# OpenROV_Controller_2_7.net
KiCad netlist of a schematic drawn in EAGLE
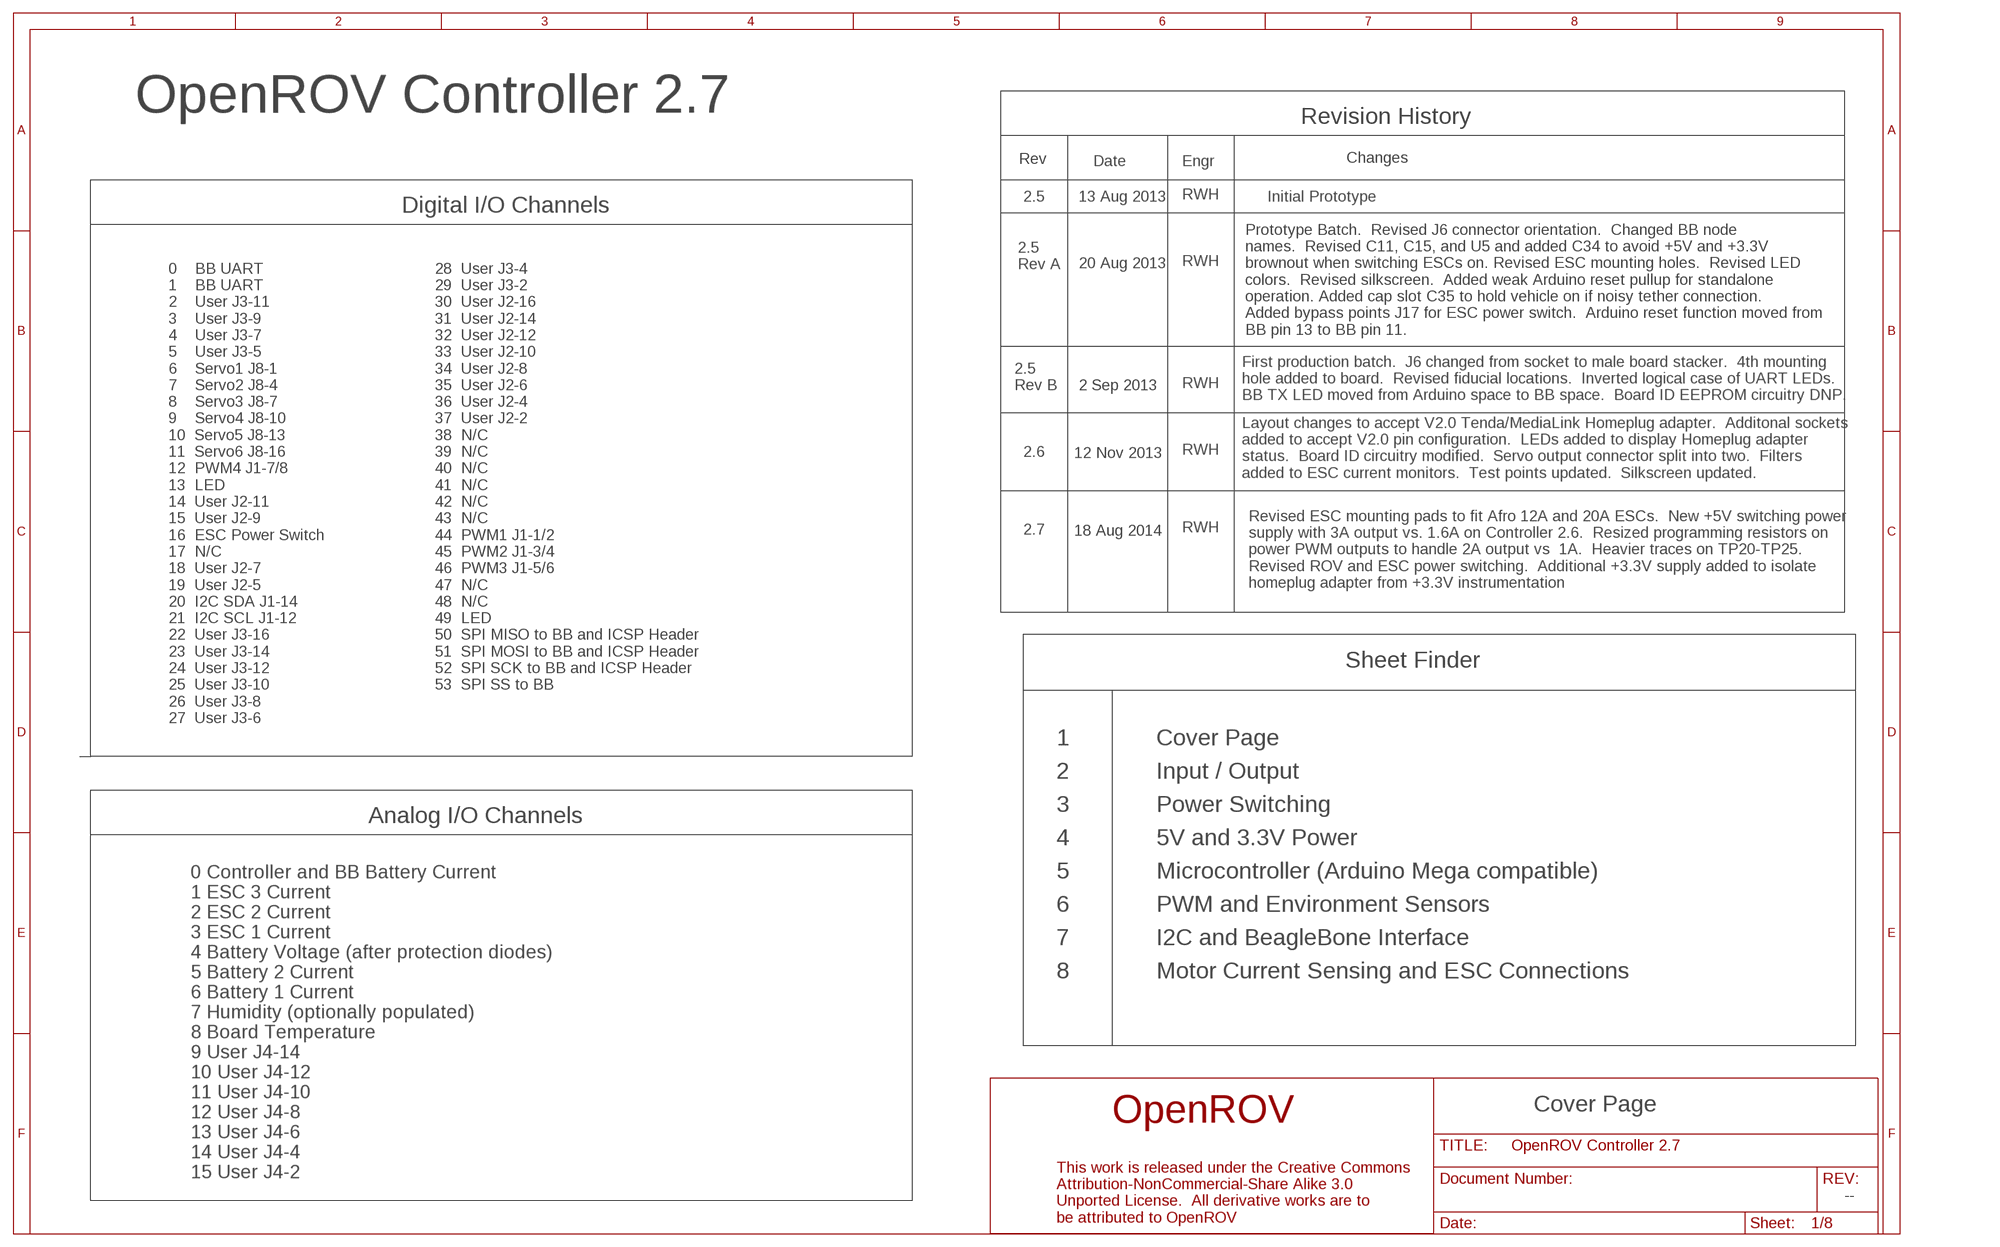
[diagram p0: schematic, sheet 1]
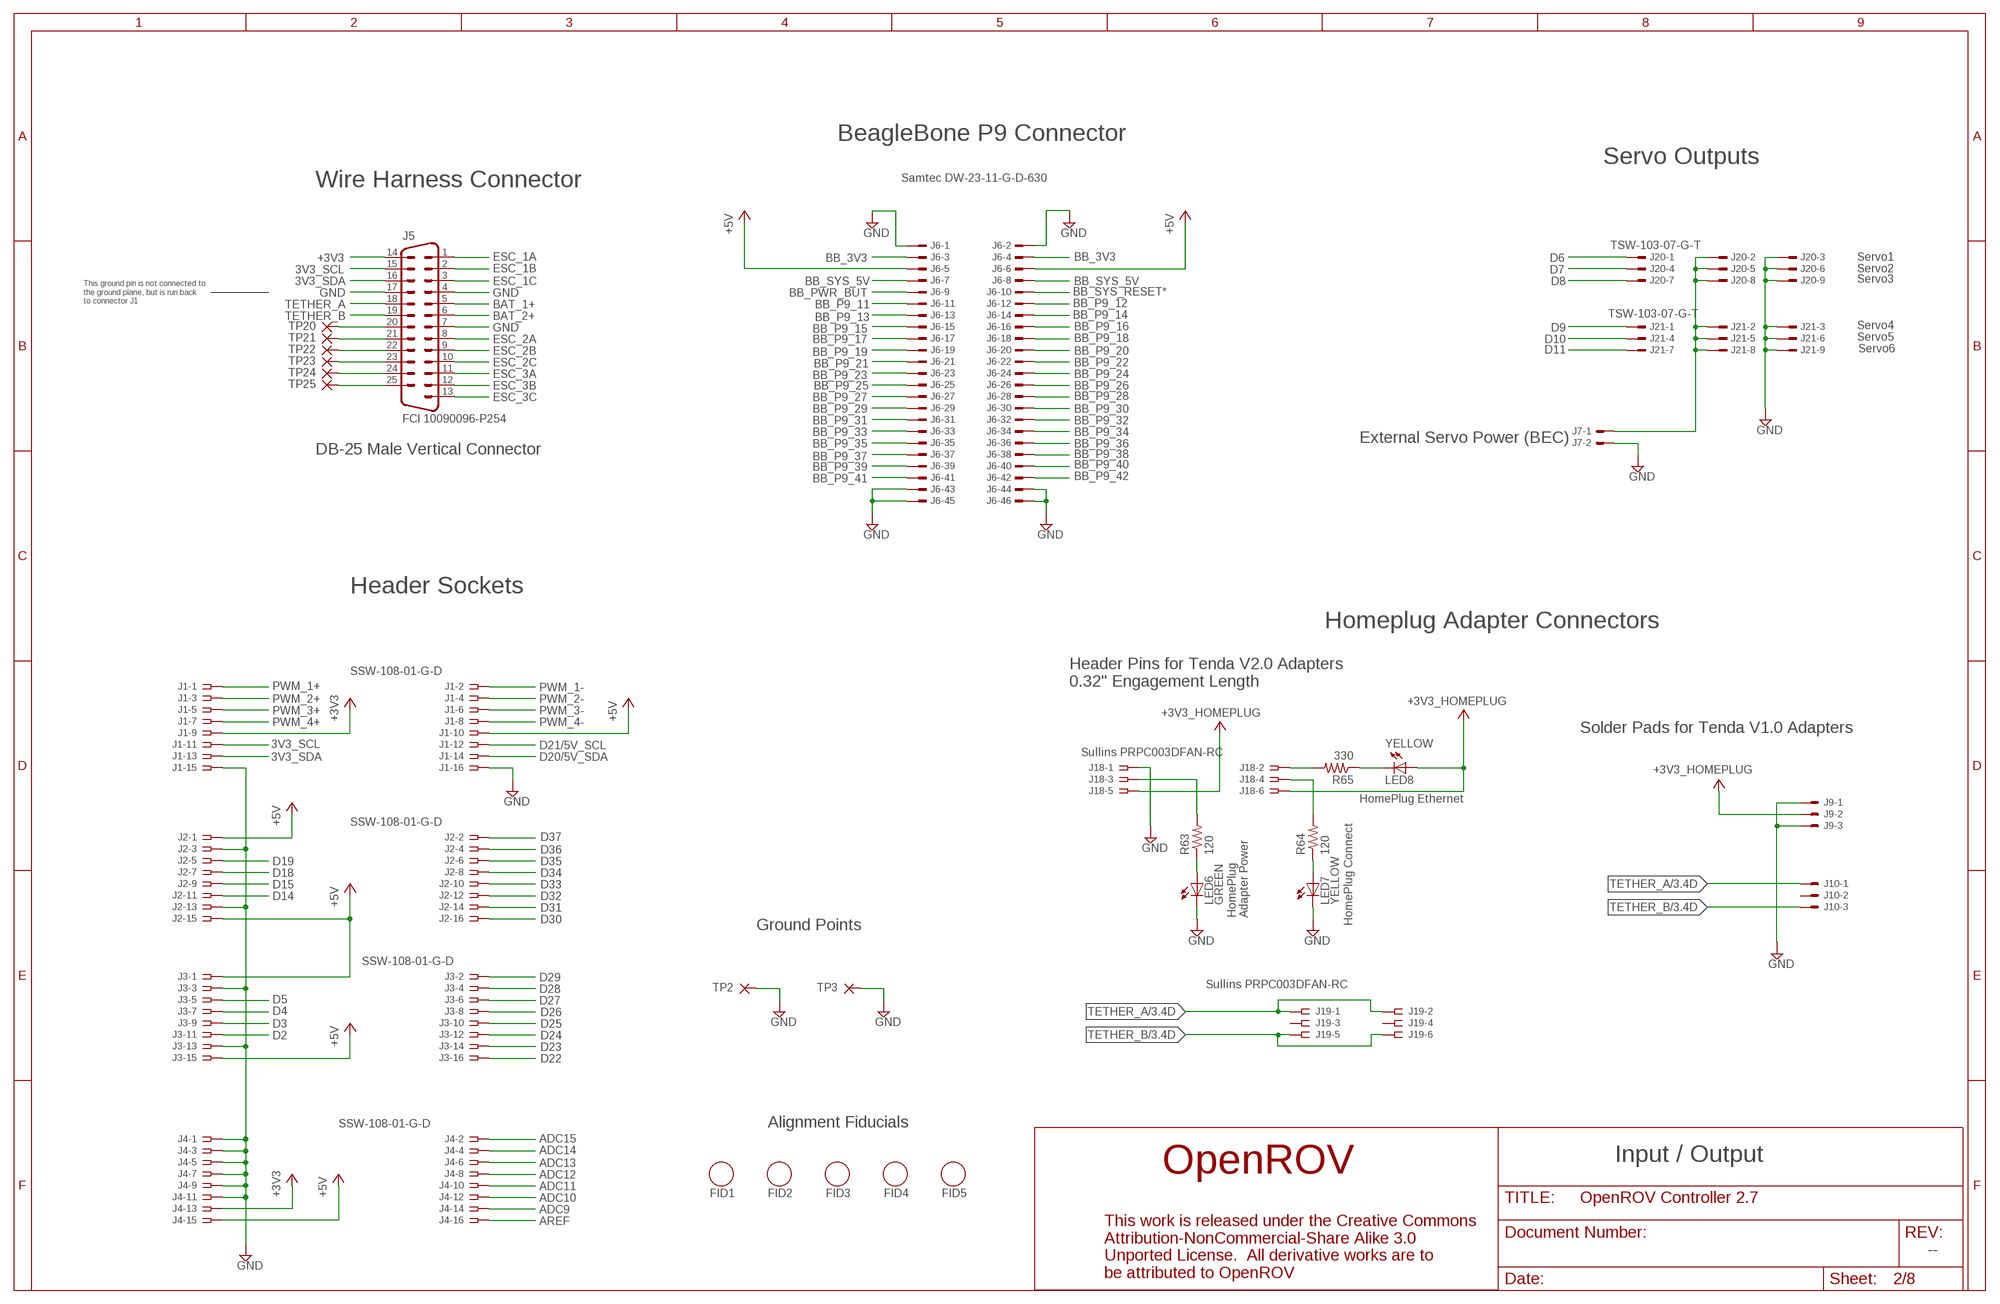
[diagram p1: schematic, sheet 2]
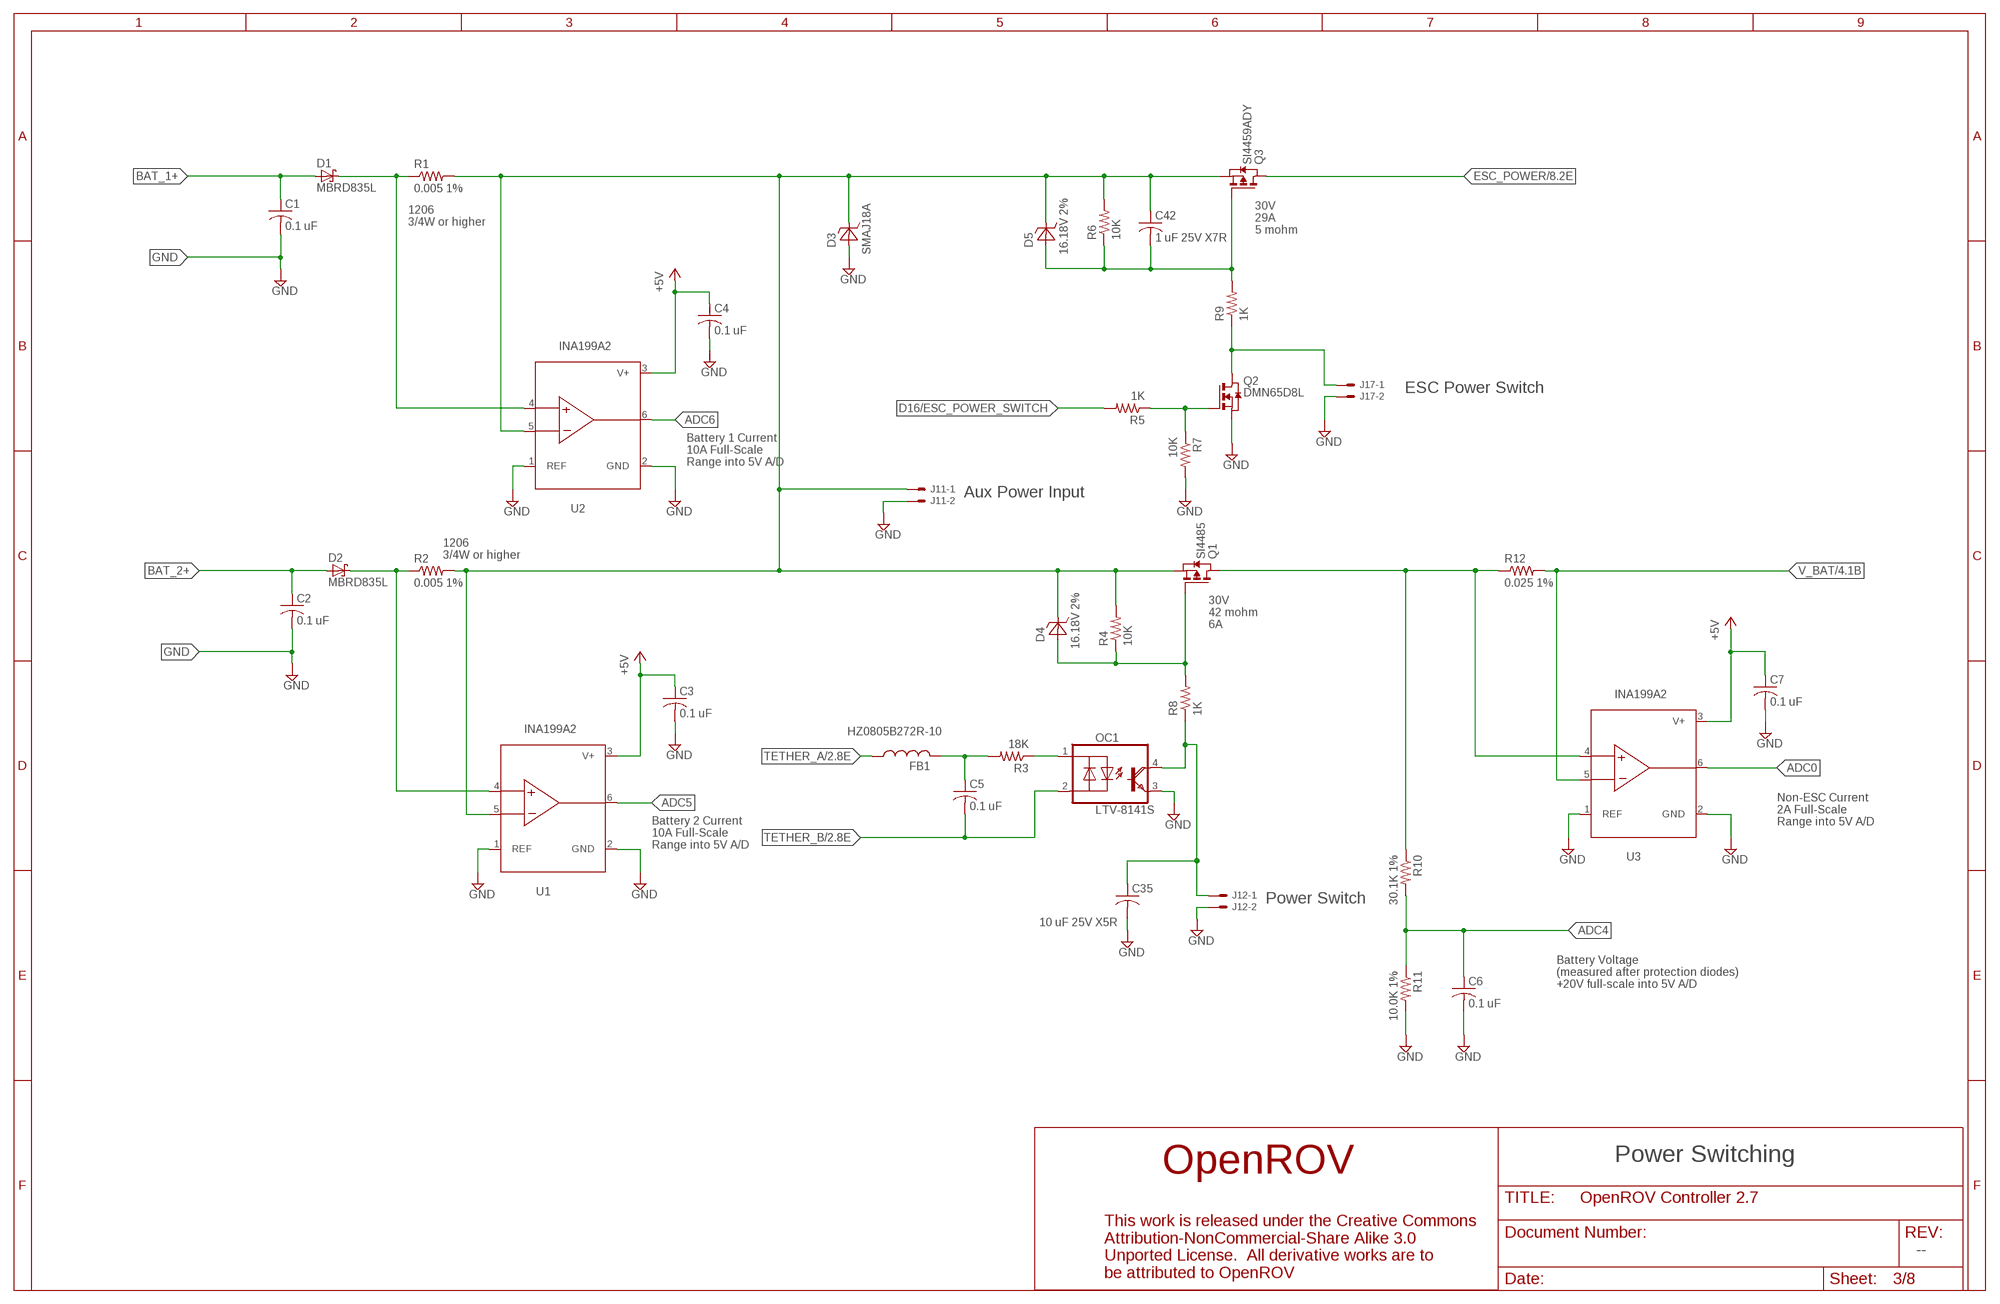
[diagram p2: schematic, sheet 3]
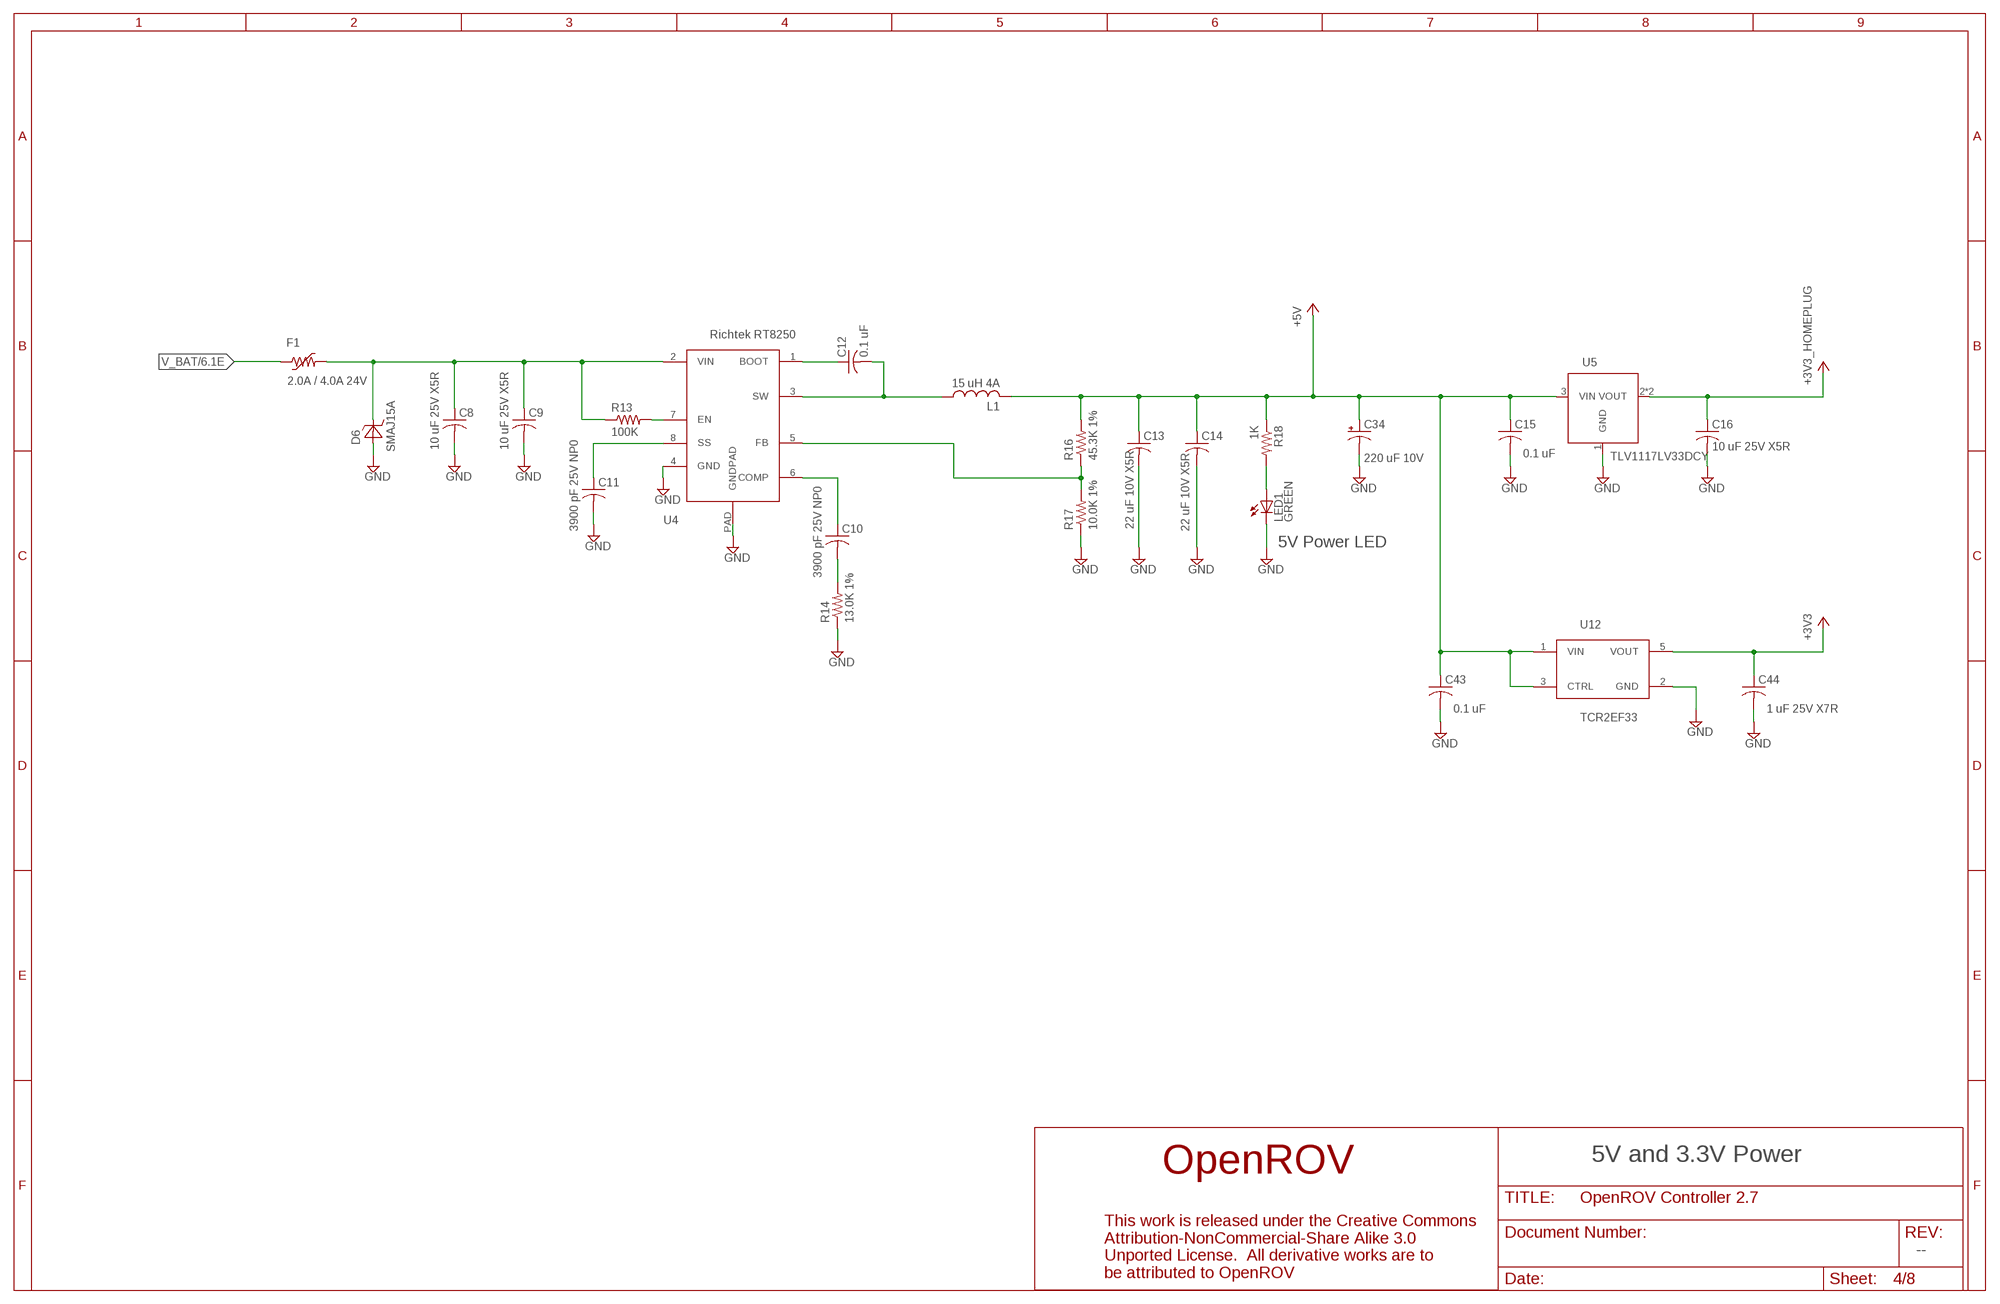
[diagram p3: schematic, sheet 4]
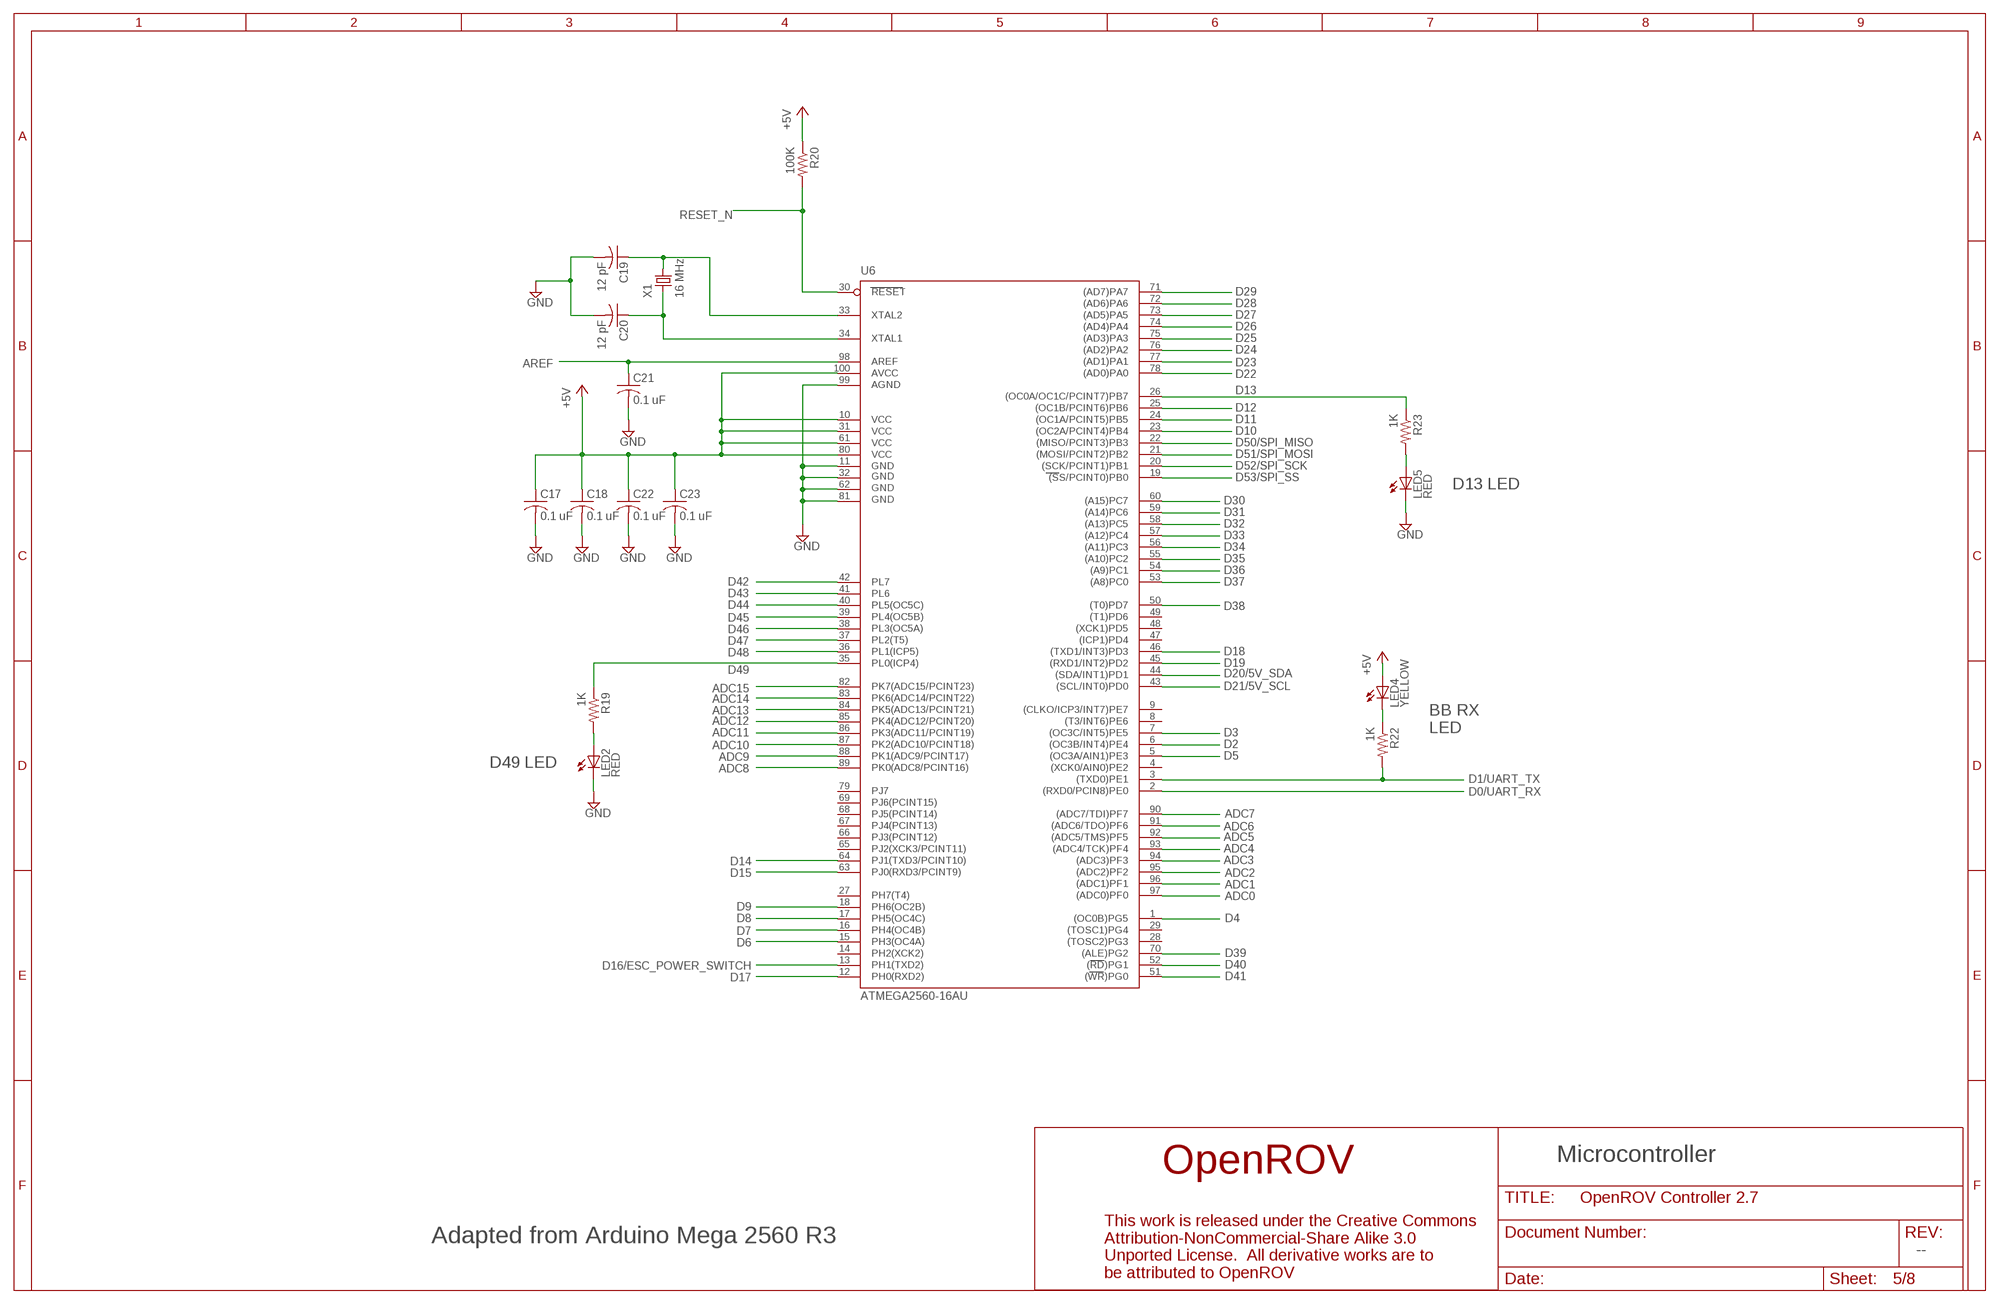
[diagram p4: schematic, sheet 5]
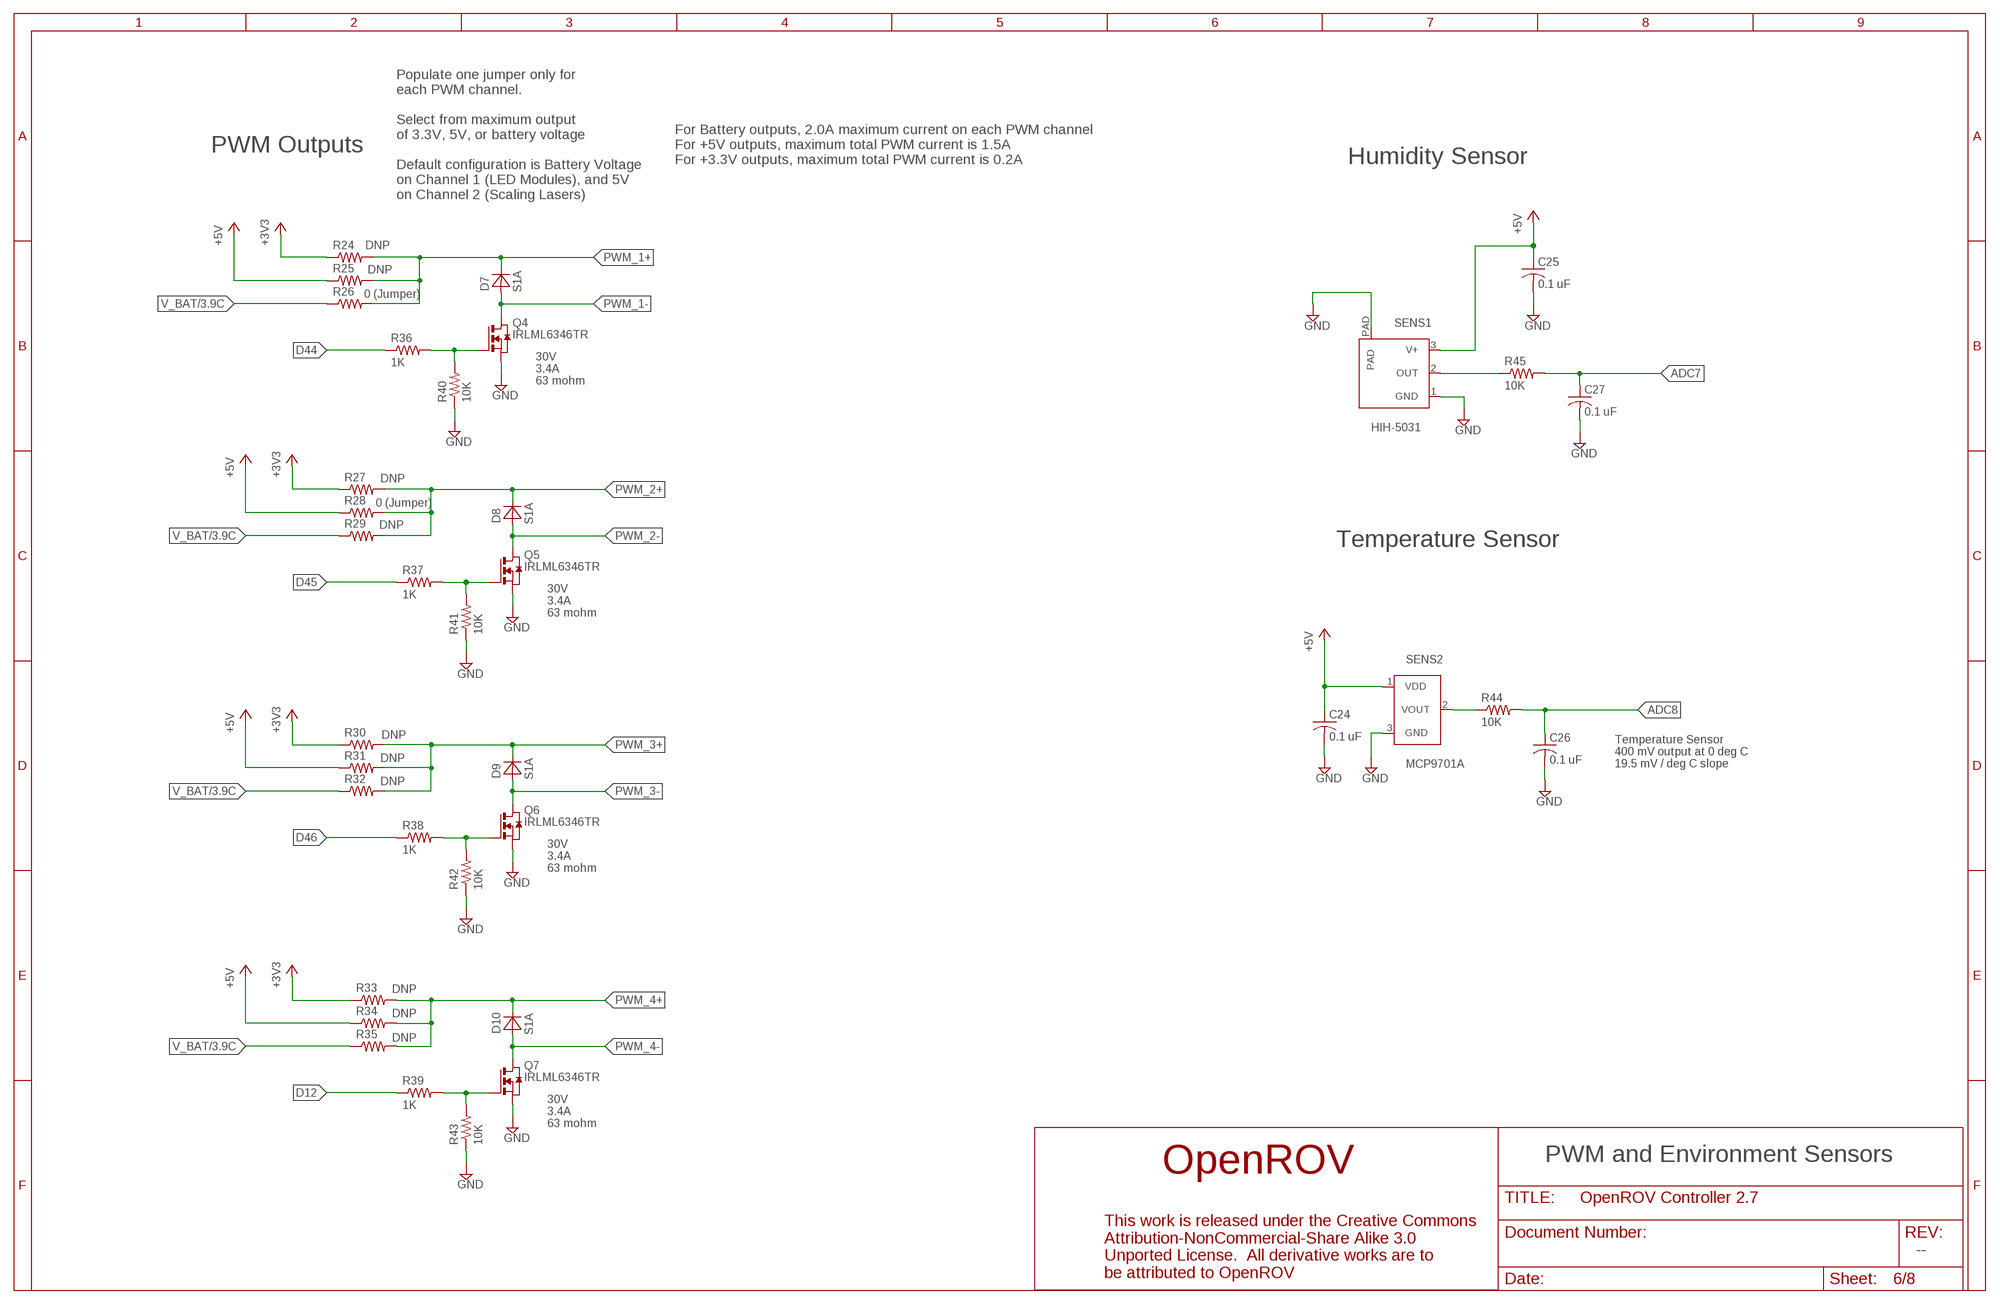
[diagram p5: schematic, sheet 6]
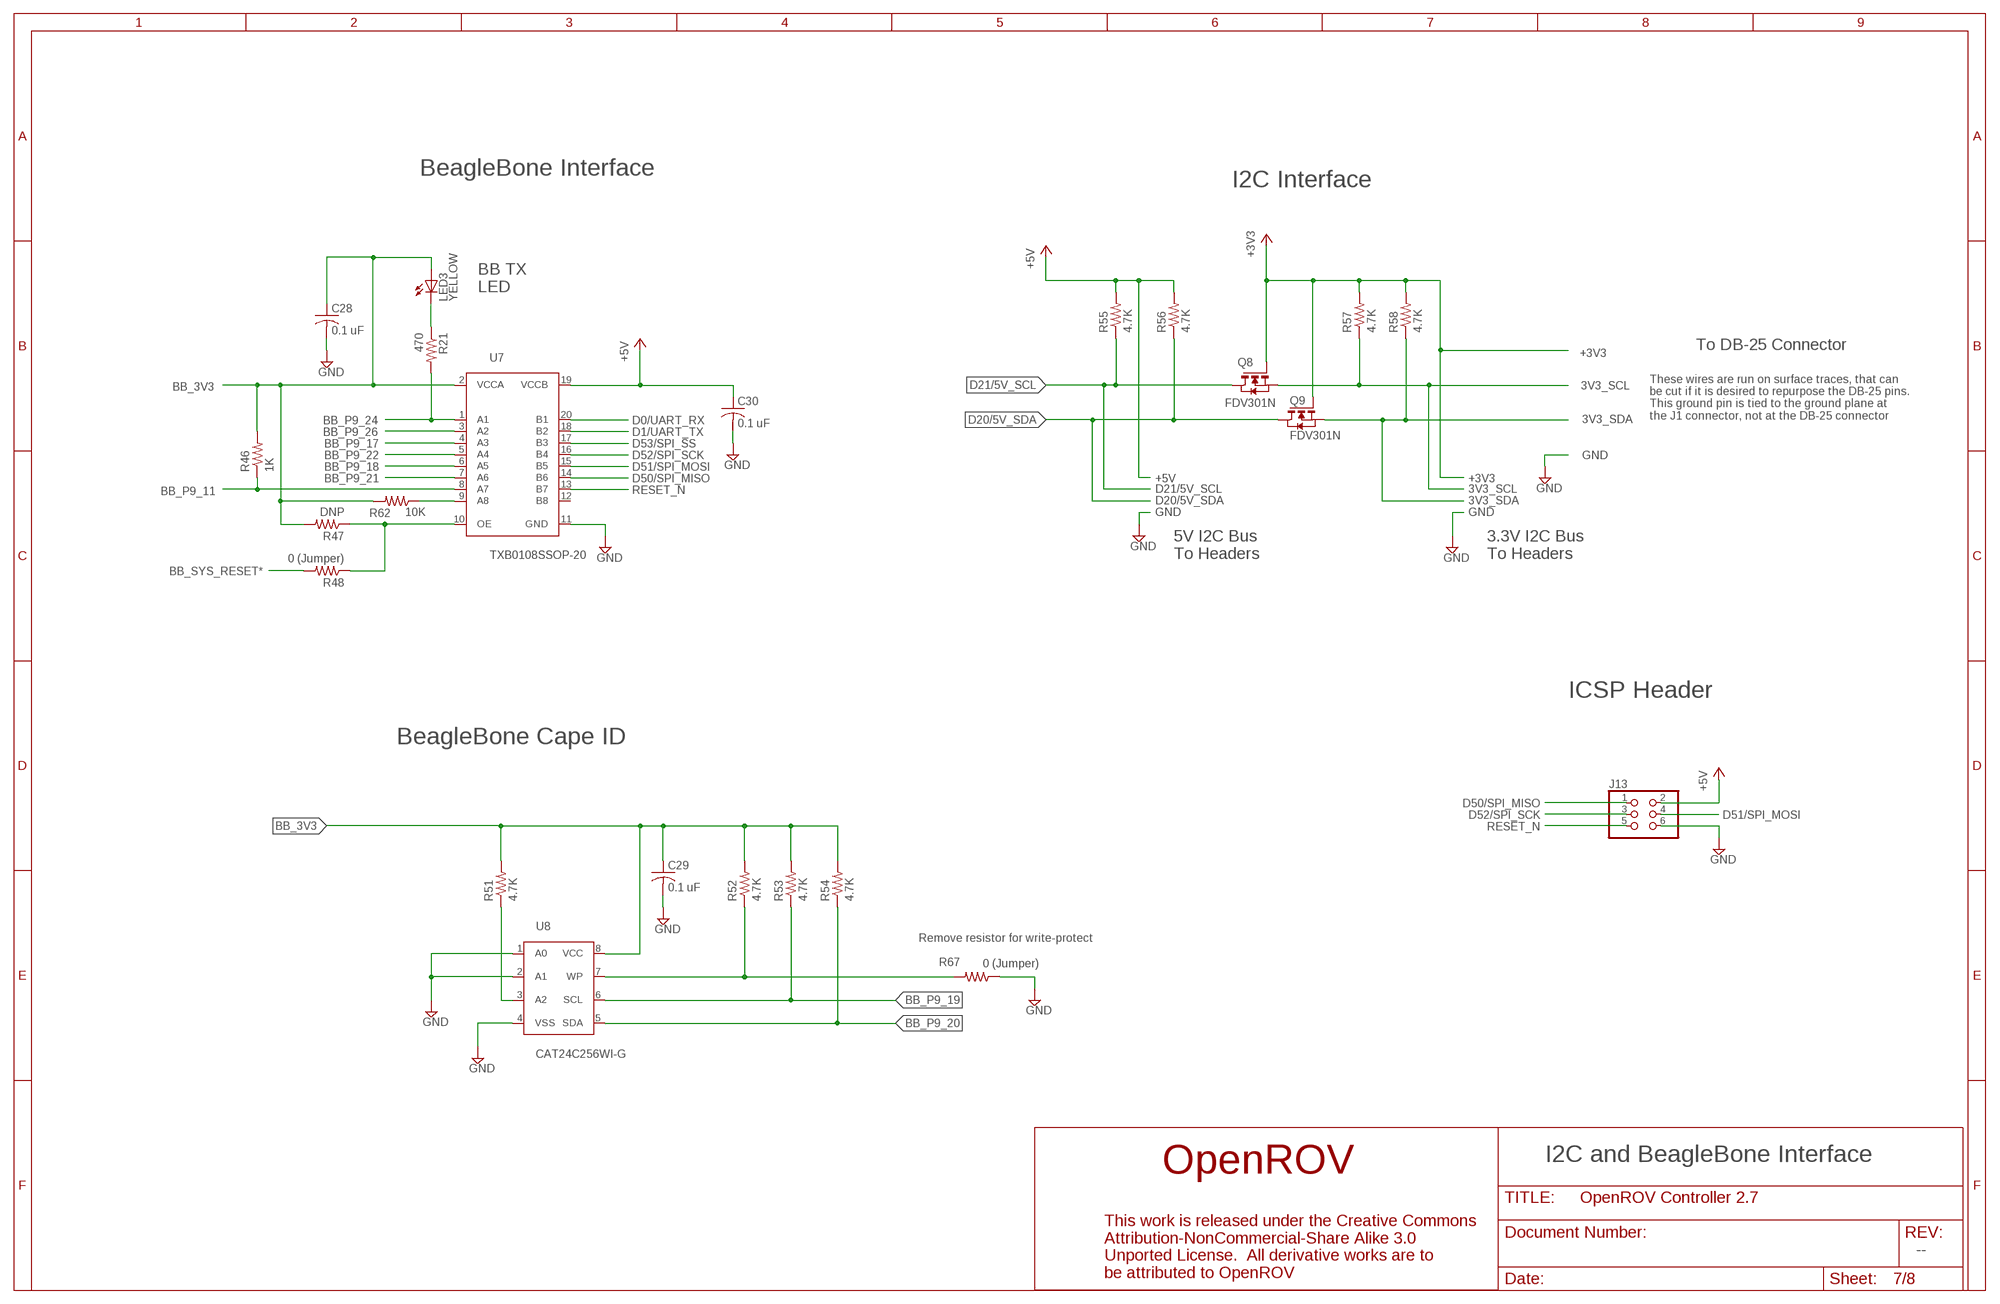
[diagram p6: schematic, sheet 7]
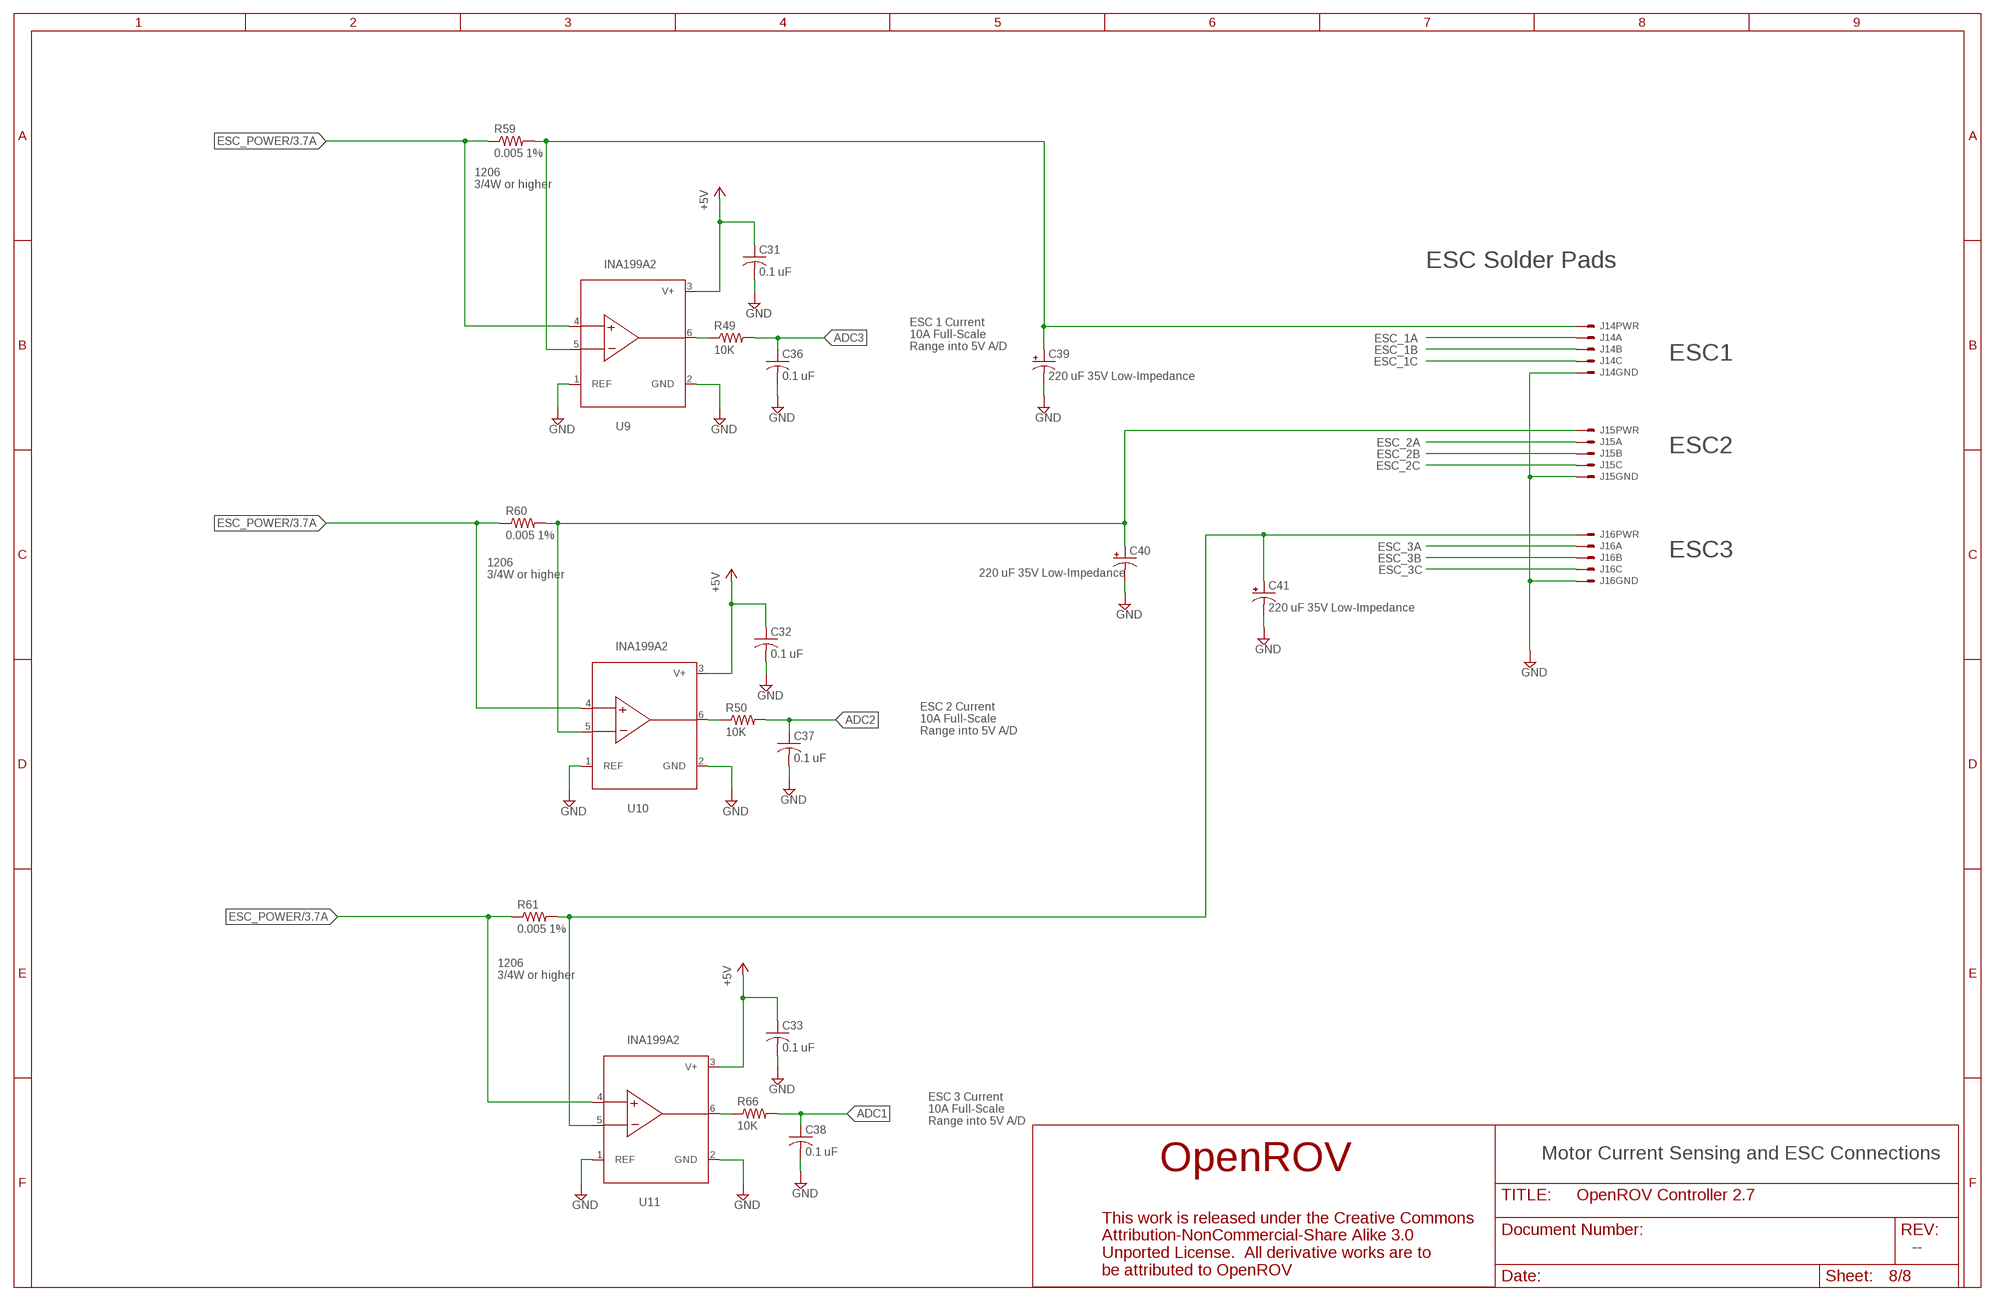
[diagram p7: schematic, sheet 8]

(export (version "E")
  (design (tool "Eeschema 10.0.6"))
  (components
    (comp (ref "FID1")
      (value "FIDUCIAL_1")
      (footprint "eagle-import:FIDUCIAL_1")
      (libsource (lib "eagle-import") (part "FIDUCIAL_1"))
    )
    (comp (ref "FID2")
      (value "FIDUCIAL_1")
      (footprint "eagle-import:FIDUCIAL_1")
      (libsource (lib "eagle-import") (part "FIDUCIAL_1"))
    )
    (comp (ref "FID3")
      (value "FIDUCIAL_1")
      (footprint "eagle-import:FIDUCIAL_1")
      (libsource (lib "eagle-import") (part "FIDUCIAL_1"))
    )
    (comp (ref "FID4")
      (value "FIDUCIAL_1")
      (footprint "eagle-import:FIDUCIAL_1")
      (libsource (lib "eagle-import") (part "FIDUCIAL_1"))
    )
    (comp (ref "FID5")
      (value "FIDUCIAL_1")
      (footprint "eagle-import:FIDUCIAL_1")
      (libsource (lib "eagle-import") (part "FIDUCIAL_1"))
    )
    (comp (ref "J1")
      (value "SSW-108-01-G-D")
      (footprint "eagle-import:SSW-108-02-S-D")
      (fields (field (name "MPN") "SSW-108-02-S-D"))
      (libsource (lib "eagle-import") (part "HDR_SOCKET_2X8"))
    )
    (comp (ref "J2")
      (value "SSW-108-01-G-D")
      (footprint "eagle-import:SSW-108-02-S-D")
      (fields (field (name "MPN") "SSW-108-02-S-D"))
      (libsource (lib "eagle-import") (part "HDR_SOCKET_2X8"))
    )
    (comp (ref "J3")
      (value "SSW-108-01-G-D")
      (footprint "eagle-import:SSW-108-02-S-D")
      (fields (field (name "MPN") "SSW-108-02-S-D"))
      (libsource (lib "eagle-import") (part "HDR_SOCKET_2X8"))
    )
    (comp (ref "J4")
      (value "SSW-108-01-G-D")
      (footprint "eagle-import:SSW-108-02-S-D")
      (fields (field (name "MPN") "SSW-108-02-S-D"))
      (libsource (lib "eagle-import") (part "HDR_SOCKET_2X8"))
    )
    (comp (ref "J5")
      (value "FCI 10090096-P254")
      (footprint "eagle-import:M25VP")
      (libsource (lib "eagle-import") (part "M25VP"))
    )
    (comp (ref "J6")
      (value "Samtec DW-23-11-G-D-630")
      (footprint "eagle-import:TSW-123-02-S-D")
      (libsource (lib "eagle-import") (part "BEAGLEBONE_PIN_HEADER"))
    )
    (comp (ref "J7")
      (value "HDR_1X2X0.100-ALT_SILK")
      (footprint "eagle-import:22-23-2021_ALT_SILK")
      (libsource (lib "eagle-import") (part "HDR_1X2X0.100-ALT_SILK"))
    )
    (comp (ref "J9")
      (value "HDR_1X3X0.100-ALT_SILK")
      (footprint "eagle-import:22-23-2031_ALT_SILK")
      (libsource (lib "eagle-import") (part "HDR_1X3X0.100-ALT_SILK"))
    )
    (comp (ref "J10")
      (value "HDR_1X3X0.100-ALT_SILK")
      (footprint "eagle-import:22-23-2031_ALT_SILK")
      (libsource (lib "eagle-import") (part "HDR_1X3X0.100-ALT_SILK"))
    )
    (comp (ref "J18")
      (value "Sullins PRPC003DFAN-RC")
      (footprint "eagle-import:SSW-103-02-S-D")
      (fields (field (name "MPN") "SSW-103-02-S-D"))
      (libsource (lib "eagle-import") (part "HDR_SOCKET_2X3"))
    )
    (comp (ref "J19")
      (value "Sullins PRPC003DFAN-RC")
      (footprint "eagle-import:SSW-103-02-S-D")
      (fields (field (name "MPN") "SSW-103-02-S-D"))
      (libsource (lib "eagle-import") (part "HDR_SOCKET_2X3"))
    )
    (comp (ref "J20")
      (value "TSW-103-07-G-T")
      (footprint "eagle-import:HDR_PINS_3X3")
      (libsource (lib "eagle-import") (part "HDR_PINS_3X3{dblquote}"))
    )
    (comp (ref "J21")
      (value "TSW-103-07-G-T")
      (footprint "eagle-import:HDR_PINS_3X3")
      (libsource (lib "eagle-import") (part "HDR_PINS_3X3{dblquote}"))
    )
    (comp (ref "LED6")
      (value "GREEN")
      (footprint "eagle-import:LED_CHIPLED_0603")
      (libsource (lib "eagle-import") (part "LED-0603"))
    )
    (comp (ref "LED7")
      (value "YELLOW")
      (footprint "eagle-import:LED_CHIPLED_0603")
      (libsource (lib "eagle-import") (part "LED-0603"))
    )
    (comp (ref "LED8")
      (value "YELLOW")
      (footprint "eagle-import:LED_CHIPLED_0603")
      (libsource (lib "eagle-import") (part "LED-0603"))
    )
    (comp (ref "R63")
      (value "120")
      (footprint "eagle-import:R0603")
      (libsource (lib "eagle-import") (part "RESISTOR-0603"))
    )
    (comp (ref "R64")
      (value "120")
      (footprint "eagle-import:R0603")
      (libsource (lib "eagle-import") (part "RESISTOR-0603"))
    )
    (comp (ref "R65")
      (value "330")
      (footprint "eagle-import:R0603")
      (libsource (lib "eagle-import") (part "RESISTOR-0603"))
    )
    (comp (ref "TP2")
      (value "TEST_PAD-1.0")
      (footprint "eagle-import:2.0_1.0")
      (libsource (lib "eagle-import") (part "TEST_PAD-1.0"))
    )
    (comp (ref "TP3")
      (value "TEST_PAD-1.0")
      (footprint "eagle-import:2.0_1.0")
      (libsource (lib "eagle-import") (part "TEST_PAD-1.0"))
    )
    (comp (ref "TP20")
      (value "TEST_PAD-1.0")
      (footprint "eagle-import:2.0_1.0")
      (libsource (lib "eagle-import") (part "TEST_PAD-1.0"))
    )
    (comp (ref "TP21")
      (value "TEST_PAD-1.0")
      (footprint "eagle-import:2.0_1.0")
      (libsource (lib "eagle-import") (part "TEST_PAD-1.0"))
    )
    (comp (ref "TP22")
      (value "TEST_PAD-1.0")
      (footprint "eagle-import:2.0_1.0")
      (libsource (lib "eagle-import") (part "TEST_PAD-1.0"))
    )
    (comp (ref "TP23")
      (value "TEST_PAD-1.0")
      (footprint "eagle-import:2.0_1.0")
      (libsource (lib "eagle-import") (part "TEST_PAD-1.0"))
    )
    (comp (ref "TP24")
      (value "TEST_PAD-1.0")
      (footprint "eagle-import:2.0_1.0")
      (libsource (lib "eagle-import") (part "TEST_PAD-1.0"))
    )
    (comp (ref "TP25")
      (value "TEST_PAD-1.0")
      (footprint "eagle-import:2.0_1.0")
      (libsource (lib "eagle-import") (part "TEST_PAD-1.0"))
    )
    (comp (ref "C8")
      (value "10 uF 25V X5R")
      (footprint "eagle-import:R0805")
      (libsource (lib "eagle-import") (part "CAP0805"))
    )
    (comp (ref "C9")
      (value "10 uF 25V X5R")
      (footprint "eagle-import:R0805")
      (libsource (lib "eagle-import") (part "CAP0805"))
    )
    (comp (ref "C10")
      (value "3900 pF 25V NP0")
      (footprint "eagle-import:R0603")
      (libsource (lib "eagle-import") (part "CAP0603"))
    )
    (comp (ref "C11")
      (value "3900 pF 25V NP0")
      (footprint "eagle-import:R0603")
      (libsource (lib "eagle-import") (part "CAP0603"))
    )
    (comp (ref "C12")
      (value "0.1 uF")
      (footprint "eagle-import:R0603")
      (libsource (lib "eagle-import") (part "CAP0603"))
    )
    (comp (ref "C13")
      (value "22 uF 10V X5R")
      (footprint "eagle-import:R0805")
      (libsource (lib "eagle-import") (part "CAP0805"))
    )
    (comp (ref "C14")
      (value "22 uF 10V X5R")
      (footprint "eagle-import:R0805")
      (libsource (lib "eagle-import") (part "CAP0805"))
    )
    (comp (ref "C15")
      (value "0.1 uF")
      (footprint "eagle-import:R0603")
      (libsource (lib "eagle-import") (part "CAP0603"))
    )
    (comp (ref "C16")
      (value "10 uF 25V X5R")
      (footprint "eagle-import:R0805")
      (libsource (lib "eagle-import") (part "CAP0805"))
    )
    (comp (ref "C34")
      (value "220 uF 10V")
      (footprint "eagle-import:NICHICON_8MM")
      (libsource (lib "eagle-import") (part "CAP-POLARIZED-NICHICON-8MM"))
    )
    (comp (ref "C43")
      (value "0.1 uF")
      (footprint "eagle-import:R0603")
      (libsource (lib "eagle-import") (part "CAP0603"))
    )
    (comp (ref "C44")
      (value "1 uF 25V X7R")
      (footprint "eagle-import:R0603")
      (libsource (lib "eagle-import") (part "CAP0603"))
    )
    (comp (ref "D6")
      (value "SMAJ15A")
      (footprint "eagle-import:DO214AC")
      (libsource (lib "eagle-import") (part "ZENER-TVSDO-214AC"))
    )
    (comp (ref "F1")
      (value "2.0A / 4.0A 24V")
      (footprint "eagle-import:R2920")
      (libsource (lib "eagle-import") (part "POLYFUSE-2920"))
    )
    (comp (ref "L1")
      (value "15 uH 4A")
      (footprint "eagle-import:INDUCTOR_BOURNS_12X0")
      (libsource (lib "eagle-import") (part "INDUCTOR-BOURNS-12X0"))
    )
    (comp (ref "LED1")
      (value "GREEN")
      (footprint "eagle-import:LED_CHIPLED_0603")
      (libsource (lib "eagle-import") (part "LED-0603"))
    )
    (comp (ref "R13")
      (value "100K")
      (footprint "eagle-import:R0603")
      (libsource (lib "eagle-import") (part "RESISTOR-0603"))
    )
    (comp (ref "R14")
      (value "13.0K 1%")
      (footprint "eagle-import:R0603")
      (libsource (lib "eagle-import") (part "RESISTOR-0603"))
    )
    (comp (ref "R16")
      (value "45.3K 1%")
      (footprint "eagle-import:R0603")
      (libsource (lib "eagle-import") (part "RESISTOR-0603"))
    )
    (comp (ref "R17")
      (value "10.0K 1%")
      (footprint "eagle-import:R0603")
      (libsource (lib "eagle-import") (part "RESISTOR-0603"))
    )
    (comp (ref "R18")
      (value "1K")
      (footprint "eagle-import:R0603")
      (libsource (lib "eagle-import") (part "RESISTOR-0603"))
    )
    (comp (ref "U4")
      (value "Richtek RT8250")
      (footprint "eagle-import:SO8-THERMAL")
      (libsource (lib "eagle-import") (part "RICHTEK_82XX"))
    )
    (comp (ref "U5")
      (value "TLV1117LV33DCY")
      (footprint "eagle-import:SOT223")
      (libsource (lib "eagle-import") (part "AP1117SOT223"))
    )
    (comp (ref "U12")
      (value "TCR2EF33")
      (footprint "eagle-import:SOT23-5L")
      (libsource (lib "eagle-import") (part "TCR2EF"))
    )
    (comp (ref "C17")
      (value "0.1 uF")
      (footprint "eagle-import:R0603")
      (libsource (lib "eagle-import") (part "CAP0603"))
    )
    (comp (ref "C18")
      (value "0.1 uF")
      (footprint "eagle-import:R0603")
      (libsource (lib "eagle-import") (part "CAP0603"))
    )
    (comp (ref "C19")
      (value "12 pF")
      (footprint "eagle-import:R0603")
      (libsource (lib "eagle-import") (part "CAP0603"))
    )
    (comp (ref "C20")
      (value "12 pF")
      (footprint "eagle-import:R0603")
      (libsource (lib "eagle-import") (part "CAP0603"))
    )
    (comp (ref "C21")
      (value "0.1 uF")
      (footprint "eagle-import:R0603")
      (libsource (lib "eagle-import") (part "CAP0603"))
    )
    (comp (ref "C22")
      (value "0.1 uF")
      (footprint "eagle-import:R0603")
      (libsource (lib "eagle-import") (part "CAP0603"))
    )
    (comp (ref "C23")
      (value "0.1 uF")
      (footprint "eagle-import:R0603")
      (libsource (lib "eagle-import") (part "CAP0603"))
    )
    (comp (ref "LED2")
      (value "RED")
      (footprint "eagle-import:LED_CHIPLED_0603")
      (libsource (lib "eagle-import") (part "LED-0603"))
    )
    (comp (ref "LED4")
      (value "YELLOW")
      (footprint "eagle-import:LED_CHIPLED_0603")
      (libsource (lib "eagle-import") (part "LED-0603"))
    )
    (comp (ref "LED5")
      (value "RED")
      (footprint "eagle-import:LED_CHIPLED_0603")
      (libsource (lib "eagle-import") (part "LED-0603"))
    )
    (comp (ref "R19")
      (value "1K")
      (footprint "eagle-import:R0603")
      (libsource (lib "eagle-import") (part "RESISTOR-0603"))
    )
    (comp (ref "R20")
      (value "100K")
      (footprint "eagle-import:R0603")
      (libsource (lib "eagle-import") (part "RESISTOR-0603"))
    )
    (comp (ref "R22")
      (value "1K")
      (footprint "eagle-import:R0603")
      (libsource (lib "eagle-import") (part "RESISTOR-0603"))
    )
    (comp (ref "R23")
      (value "1K")
      (footprint "eagle-import:R0603")
      (libsource (lib "eagle-import") (part "RESISTOR-0603"))
    )
    (comp (ref "U6")
      (value "ATMEGA2560-16AU")
      (footprint "eagle-import:SMARTPRJ_TQFP100")
      (libsource (lib "eagle-import") (part "SMARTPRJ_ATMEGA2560AU2560-16"))
    )
    (comp (ref "X1")
      (value "16 MHz")
      (footprint "eagle-import:DISCRETE_2P-SMD-5X3.2")
      (libsource (lib "eagle-import") (part "CRYSTAL-53.2"))
    )
    (comp (ref "C28")
      (value "0.1 uF")
      (footprint "eagle-import:R0603")
      (libsource (lib "eagle-import") (part "CAP0603"))
    )
    (comp (ref "C29")
      (value "0.1 uF")
      (footprint "eagle-import:R0603")
      (libsource (lib "eagle-import") (part "CAP0603"))
    )
    (comp (ref "C30")
      (value "0.1 uF")
      (footprint "eagle-import:R0603")
      (libsource (lib "eagle-import") (part "CAP0603"))
    )
    (comp (ref "J13")
      (value "HDR_PINS_2X3")
      (footprint "eagle-import:HDR_PINS_2X3")
      (libsource (lib "eagle-import") (part "HDR_PINS_2X3"))
    )
    (comp (ref "LED3")
      (value "YELLOW")
      (footprint "eagle-import:LED_CHIPLED_0603")
      (libsource (lib "eagle-import") (part "LED-0603"))
    )
    (comp (ref "Q8")
      (value "FDV301N")
      (footprint "eagle-import:SOT23")
      (libsource (lib "eagle-import") (part "NMOS-FETSOT23"))
    )
    (comp (ref "Q9")
      (value "FDV301N")
      (footprint "eagle-import:SOT23")
      (libsource (lib "eagle-import") (part "NMOS-FETSOT23"))
    )
    (comp (ref "R21")
      (value "470")
      (footprint "eagle-import:R0603")
      (libsource (lib "eagle-import") (part "RESISTOR-0603"))
    )
    (comp (ref "R46")
      (value "1K")
      (footprint "eagle-import:R0603")
      (libsource (lib "eagle-import") (part "RESISTOR-0603"))
    )
    (comp (ref "R47")
      (value "DNP")
      (footprint "eagle-import:R0603")
      (libsource (lib "eagle-import") (part "RESISTOR-0603"))
    )
    (comp (ref "R48")
      (value "0 (Jumper)")
      (footprint "eagle-import:R0603")
      (libsource (lib "eagle-import") (part "RESISTOR-0603"))
    )
    (comp (ref "R51")
      (value "4.7K")
      (footprint "eagle-import:R0603")
      (libsource (lib "eagle-import") (part "RESISTOR-0603"))
    )
    (comp (ref "R52")
      (value "4.7K")
      (footprint "eagle-import:R0603")
      (libsource (lib "eagle-import") (part "RESISTOR-0603"))
    )
    (comp (ref "R53")
      (value "4.7K")
      (footprint "eagle-import:R0603")
      (libsource (lib "eagle-import") (part "RESISTOR-0603"))
    )
    (comp (ref "R54")
      (value "4.7K")
      (footprint "eagle-import:R0603")
      (libsource (lib "eagle-import") (part "RESISTOR-0603"))
    )
    (comp (ref "R55")
      (value "4.7K")
      (footprint "eagle-import:R0603")
      (libsource (lib "eagle-import") (part "RESISTOR-0603"))
    )
    (comp (ref "R56")
      (value "4.7K")
      (footprint "eagle-import:R0603")
      (libsource (lib "eagle-import") (part "RESISTOR-0603"))
    )
    (comp (ref "R57")
      (value "4.7K")
      (footprint "eagle-import:R0603")
      (libsource (lib "eagle-import") (part "RESISTOR-0603"))
    )
    (comp (ref "R58")
      (value "4.7K")
      (footprint "eagle-import:R0603")
      (libsource (lib "eagle-import") (part "RESISTOR-0603"))
    )
    (comp (ref "R62")
      (value "10K")
      (footprint "eagle-import:R0603")
      (libsource (lib "eagle-import") (part "RESISTOR-0603"))
    )
    (comp (ref "R67")
      (value "0 (Jumper)")
      (footprint "eagle-import:R0603")
      (libsource (lib "eagle-import") (part "RESISTOR-0603"))
    )
    (comp (ref "U7")
      (value "TXB0108SSOP-20")
      (footprint "eagle-import:SSOP-20")
      (libsource (lib "eagle-import") (part "TXB0108SSOP-20"))
    )
    (comp (ref "U8")
      (value "CAT24C256WI-G")
      (footprint "eagle-import:SO8")
      (libsource (lib "eagle-import") (part "CAT24C256WI-G"))
    )
    (comp (ref "C24")
      (value "0.1 uF")
      (footprint "eagle-import:R0603")
      (libsource (lib "eagle-import") (part "CAP0603"))
    )
    (comp (ref "C25")
      (value "0.1 uF")
      (footprint "eagle-import:R0603")
      (libsource (lib "eagle-import") (part "CAP0603"))
    )
    (comp (ref "C26")
      (value "0.1 uF")
      (footprint "eagle-import:R0603")
      (libsource (lib "eagle-import") (part "CAP0603"))
    )
    (comp (ref "C27")
      (value "0.1 uF")
      (footprint "eagle-import:R0603")
      (libsource (lib "eagle-import") (part "CAP0603"))
    )
    (comp (ref "D7")
      (value "S1A")
      (footprint "eagle-import:DO214AC")
      (libsource (lib "eagle-import") (part "DIODE"))
    )
    (comp (ref "D8")
      (value "S1A")
      (footprint "eagle-import:DO214AC")
      (libsource (lib "eagle-import") (part "DIODE"))
    )
    (comp (ref "D9")
      (value "S1A")
      (footprint "eagle-import:DO214AC")
      (libsource (lib "eagle-import") (part "DIODE"))
    )
    (comp (ref "D10")
      (value "S1A")
      (footprint "eagle-import:DO214AC")
      (libsource (lib "eagle-import") (part "DIODE"))
    )
    (comp (ref "Q4")
      (value "IRLML6346TR")
      (footprint "eagle-import:SOT23")
      (libsource (lib "eagle-import") (part "NMOS-FETSOT23"))
    )
    (comp (ref "Q5")
      (value "IRLML6346TR")
      (footprint "eagle-import:SOT23")
      (libsource (lib "eagle-import") (part "NMOS-FETSOT23"))
    )
    (comp (ref "Q6")
      (value "IRLML6346TR")
      (footprint "eagle-import:SOT23")
      (libsource (lib "eagle-import") (part "NMOS-FETSOT23"))
    )
    (comp (ref "Q7")
      (value "IRLML6346TR")
      (footprint "eagle-import:SOT23")
      (libsource (lib "eagle-import") (part "NMOS-FETSOT23"))
    )
    (comp (ref "R24")
      (value "DNP")
      (footprint "eagle-import:R0805")
      (libsource (lib "eagle-import") (part "RESISTOR-0805"))
    )
    (comp (ref "R25")
      (value "DNP")
      (footprint "eagle-import:R0805")
      (libsource (lib "eagle-import") (part "RESISTOR-0805"))
    )
    (comp (ref "R26")
      (value "0 (Jumper)")
      (footprint "eagle-import:R0805")
      (libsource (lib "eagle-import") (part "RESISTOR-0805"))
    )
    (comp (ref "R27")
      (value "DNP")
      (footprint "eagle-import:R0805")
      (libsource (lib "eagle-import") (part "RESISTOR-0805"))
    )
    (comp (ref "R28")
      (value "0 (Jumper)")
      (footprint "eagle-import:R0805")
      (libsource (lib "eagle-import") (part "RESISTOR-0805"))
    )
    (comp (ref "R29")
      (value "DNP")
      (footprint "eagle-import:R0805")
      (libsource (lib "eagle-import") (part "RESISTOR-0805"))
    )
    (comp (ref "R30")
      (value "DNP")
      (footprint "eagle-import:R0805")
      (libsource (lib "eagle-import") (part "RESISTOR-0805"))
    )
    (comp (ref "R31")
      (value "DNP")
      (footprint "eagle-import:R0805")
      (libsource (lib "eagle-import") (part "RESISTOR-0805"))
    )
    (comp (ref "R32")
      (value "DNP")
      (footprint "eagle-import:R0805")
      (libsource (lib "eagle-import") (part "RESISTOR-0805"))
    )
    (comp (ref "R33")
      (value "DNP")
      (footprint "eagle-import:R0805")
      (libsource (lib "eagle-import") (part "RESISTOR-0805"))
    )
    (comp (ref "R34")
      (value "DNP")
      (footprint "eagle-import:R0805")
      (libsource (lib "eagle-import") (part "RESISTOR-0805"))
    )
    (comp (ref "R35")
      (value "DNP")
      (footprint "eagle-import:R0805")
      (libsource (lib "eagle-import") (part "RESISTOR-0805"))
    )
    (comp (ref "R36")
      (value "1K")
      (footprint "eagle-import:R0603")
      (libsource (lib "eagle-import") (part "RESISTOR-0603"))
    )
    (comp (ref "R37")
      (value "1K")
      (footprint "eagle-import:R0603")
      (libsource (lib "eagle-import") (part "RESISTOR-0603"))
    )
    (comp (ref "R38")
      (value "1K")
      (footprint "eagle-import:R0603")
      (libsource (lib "eagle-import") (part "RESISTOR-0603"))
    )
    (comp (ref "R39")
      (value "1K")
      (footprint "eagle-import:R0603")
      (libsource (lib "eagle-import") (part "RESISTOR-0603"))
    )
    (comp (ref "R40")
      (value "10K")
      (footprint "eagle-import:R0603")
      (libsource (lib "eagle-import") (part "RESISTOR-0603"))
    )
    (comp (ref "R41")
      (value "10K")
      (footprint "eagle-import:R0603")
      (libsource (lib "eagle-import") (part "RESISTOR-0603"))
    )
    (comp (ref "R42")
      (value "10K")
      (footprint "eagle-import:R0603")
      (libsource (lib "eagle-import") (part "RESISTOR-0603"))
    )
    (comp (ref "R43")
      (value "10K")
      (footprint "eagle-import:R0603")
      (libsource (lib "eagle-import") (part "RESISTOR-0603"))
    )
    (comp (ref "R44")
      (value "10K")
      (footprint "eagle-import:R0603")
      (libsource (lib "eagle-import") (part "RESISTOR-0603"))
    )
    (comp (ref "R45")
      (value "10K")
      (footprint "eagle-import:R0603")
      (libsource (lib "eagle-import") (part "RESISTOR-0603"))
    )
    (comp (ref "SENS1")
      (value "HIH-5031")
      (footprint "eagle-import:HIH-5031")
      (libsource (lib "eagle-import") (part "HIH-5031"))
    )
    (comp (ref "SENS2")
      (value "MCP9701A")
      (footprint "eagle-import:SOT23")
      (libsource (lib "eagle-import") (part "MCP9701"))
    )
    (comp (ref "C1")
      (value "0.1 uF")
      (footprint "eagle-import:R0603")
      (libsource (lib "eagle-import") (part "CAP0603"))
    )
    (comp (ref "C2")
      (value "0.1 uF")
      (footprint "eagle-import:R0603")
      (libsource (lib "eagle-import") (part "CAP0603"))
    )
    (comp (ref "C3")
      (value "0.1 uF")
      (footprint "eagle-import:R0603")
      (libsource (lib "eagle-import") (part "CAP0603"))
    )
    (comp (ref "C4")
      (value "0.1 uF")
      (footprint "eagle-import:R0603")
      (libsource (lib "eagle-import") (part "CAP0603"))
    )
    (comp (ref "C5")
      (value "0.1 uF")
      (footprint "eagle-import:R0603")
      (libsource (lib "eagle-import") (part "CAP0603"))
    )
    (comp (ref "C6")
      (value "0.1 uF")
      (footprint "eagle-import:R0603")
      (libsource (lib "eagle-import") (part "CAP0603"))
    )
    (comp (ref "C7")
      (value "0.1 uF")
      (footprint "eagle-import:R0603")
      (libsource (lib "eagle-import") (part "CAP0603"))
    )
    (comp (ref "C35")
      (value "10 uF 25V X5R")
      (footprint "eagle-import:R0805")
      (libsource (lib "eagle-import") (part "CAP0805"))
    )
    (comp (ref "C42")
      (value "1 uF 25V X7R")
      (footprint "eagle-import:R0603")
      (libsource (lib "eagle-import") (part "CAP0603"))
    )
    (comp (ref "D1")
      (value "MBRD835L")
      (footprint "eagle-import:DPAK")
      (libsource (lib "eagle-import") (part "SCHOTTKYDPAK"))
    )
    (comp (ref "D2")
      (value "MBRD835L")
      (footprint "eagle-import:DPAK")
      (libsource (lib "eagle-import") (part "SCHOTTKYDPAK"))
    )
    (comp (ref "D3")
      (value "SMAJ18A")
      (footprint "eagle-import:DO214AC")
      (libsource (lib "eagle-import") (part "ZENER-TVSDO-214AC"))
    )
    (comp (ref "D4")
      (value "16.18V 2%")
      (footprint "eagle-import:SOD323")
      (libsource (lib "eagle-import") (part "ZENER-TVSSOD323"))
    )
    (comp (ref "D5")
      (value "16.18V 2%")
      (footprint "eagle-import:SOD323")
      (libsource (lib "eagle-import") (part "ZENER-TVSSOD323"))
    )
    (comp (ref "FB1")
      (value "HZ0805B272R-10")
      (footprint "eagle-import:R0805")
      (libsource (lib "eagle-import") (part "FERRITESIZE_0805"))
    )
    (comp (ref "J11")
      (value "HDR_1X2X0.100-ALT_SILK")
      (footprint "eagle-import:22-23-2021_ALT_SILK")
      (libsource (lib "eagle-import") (part "HDR_1X2X0.100-ALT_SILK"))
    )
    (comp (ref "J12")
      (value "HDR_1X2X0.100-ALT_SILK")
      (footprint "eagle-import:22-23-2021_ALT_SILK")
      (libsource (lib "eagle-import") (part "HDR_1X2X0.100-ALT_SILK"))
    )
    (comp (ref "J17")
      (value "HDR_1X2X0.100-ALT_SILK")
      (footprint "eagle-import:22-23-2021_ALT_SILK")
      (libsource (lib "eagle-import") (part "HDR_1X2X0.100-ALT_SILK"))
    )
    (comp (ref "OC1")
      (value "LTV-8141S")
      (footprint "eagle-import:DIL4-SMD")
      (libsource (lib "eagle-import") (part "LTV-8141S"))
    )
    (comp (ref "Q1")
      (value "SI4485")
      (footprint "eagle-import:SO8")
      (libsource (lib "eagle-import") (part "PMOS-FET"))
    )
    (comp (ref "Q2")
      (value "DMN65D8L")
      (footprint "eagle-import:SOT23")
      (libsource (lib "eagle-import") (part "NMOS-FETSOT23"))
    )
    (comp (ref "Q3")
      (value "SI4459ADY")
      (footprint "eagle-import:SO8")
      (libsource (lib "eagle-import") (part "PMOS-FET"))
    )
    (comp (ref "R1")
      (value "0.005 1%")
      (footprint "eagle-import:R1206")
      (libsource (lib "eagle-import") (part "RESISTOR-1206"))
    )
    (comp (ref "R2")
      (value "0.005 1%")
      (footprint "eagle-import:R1206")
      (libsource (lib "eagle-import") (part "RESISTOR-1206"))
    )
    (comp (ref "R3")
      (value "18K")
      (footprint "eagle-import:R0603")
      (libsource (lib "eagle-import") (part "RESISTOR-0603"))
    )
    (comp (ref "R4")
      (value "10K")
      (footprint "eagle-import:R0603")
      (libsource (lib "eagle-import") (part "RESISTOR-0603"))
    )
    (comp (ref "R5")
      (value "1K")
      (footprint "eagle-import:R0603")
      (libsource (lib "eagle-import") (part "RESISTOR-0603"))
    )
    (comp (ref "R6")
      (value "10K")
      (footprint "eagle-import:R0603")
      (libsource (lib "eagle-import") (part "RESISTOR-0603"))
    )
    (comp (ref "R7")
      (value "10K")
      (footprint "eagle-import:R0603")
      (libsource (lib "eagle-import") (part "RESISTOR-0603"))
    )
    (comp (ref "R8")
      (value "1K")
      (footprint "eagle-import:R0603")
      (libsource (lib "eagle-import") (part "RESISTOR-0603"))
    )
    (comp (ref "R9")
      (value "1K")
      (footprint "eagle-import:R0603")
      (libsource (lib "eagle-import") (part "RESISTOR-0603"))
    )
    (comp (ref "R10")
      (value "30.1K 1%")
      (footprint "eagle-import:R0603")
      (libsource (lib "eagle-import") (part "RESISTOR-0603"))
    )
    (comp (ref "R11")
      (value "10.0K 1%")
      (footprint "eagle-import:R0603")
      (libsource (lib "eagle-import") (part "RESISTOR-0603"))
    )
    (comp (ref "R12")
      (value "0.025 1%")
      (footprint "eagle-import:R0805")
      (libsource (lib "eagle-import") (part "RESISTOR-0805"))
    )
    (comp (ref "U1")
      (value "INA199A2")
      (footprint "eagle-import:SC70-6L")
      (libsource (lib "eagle-import") (part "INA199"))
    )
    (comp (ref "U2")
      (value "INA199A2")
      (footprint "eagle-import:SC70-6L")
      (libsource (lib "eagle-import") (part "INA199"))
    )
    (comp (ref "U3")
      (value "INA199A2")
      (footprint "eagle-import:SC70-6L")
      (libsource (lib "eagle-import") (part "INA199"))
    )
    (comp (ref "C31")
      (value "0.1 uF")
      (footprint "eagle-import:R0603")
      (libsource (lib "eagle-import") (part "CAP0603"))
    )
    (comp (ref "C32")
      (value "0.1 uF")
      (footprint "eagle-import:R0603")
      (libsource (lib "eagle-import") (part "CAP0603"))
    )
    (comp (ref "C33")
      (value "0.1 uF")
      (footprint "eagle-import:R0603")
      (libsource (lib "eagle-import") (part "CAP0603"))
    )
    (comp (ref "C36")
      (value "0.1 uF")
      (footprint "eagle-import:R0603")
      (libsource (lib "eagle-import") (part "CAP0603"))
    )
    (comp (ref "C37")
      (value "0.1 uF")
      (footprint "eagle-import:R0603")
      (libsource (lib "eagle-import") (part "CAP0603"))
    )
    (comp (ref "C38")
      (value "0.1 uF")
      (footprint "eagle-import:R0603")
      (libsource (lib "eagle-import") (part "CAP0603"))
    )
    (comp (ref "C39")
      (value "220 uF 35V Low-Impedance")
      (footprint "eagle-import:NICHICON_10MM")
      (libsource (lib "eagle-import") (part "CAP-POLARIZED-NICHICON-10MM"))
    )
    (comp (ref "C40")
      (value "220 uF 35V Low-Impedance")
      (footprint "eagle-import:NICHICON_10MM")
      (libsource (lib "eagle-import") (part "CAP-POLARIZED-NICHICON-10MM"))
    )
    (comp (ref "C41")
      (value "220 uF 35V Low-Impedance")
      (footprint "eagle-import:NICHICON_10MM")
      (libsource (lib "eagle-import") (part "CAP-POLARIZED-NICHICON-10MM"))
    )
    (comp (ref "J14")
      (value "ESC_PADS-AFRO-12/20A-ESC1")
      (footprint "eagle-import:AFRO-ESC-12_20A-ESC1")
      (libsource (lib "eagle-import") (part "ESC_PADS-AFRO-12/20A-ESC1"))
    )
    (comp (ref "J15")
      (value "ESC_PADS-AFRO-12/20A-ESC2")
      (footprint "eagle-import:AFRO-ESC-12_20A-ESC2")
      (libsource (lib "eagle-import") (part "ESC_PADS-AFRO-12/20A-ESC2"))
    )
    (comp (ref "J16")
      (value "ESC_PADS-AFRO-12/20A-ESC3")
      (footprint "eagle-import:AFRO-ESC-12_20A-ESC3")
      (libsource (lib "eagle-import") (part "ESC_PADS-AFRO-12/20A-ESC3"))
    )
    (comp (ref "R49")
      (value "10K")
      (footprint "eagle-import:R0603")
      (libsource (lib "eagle-import") (part "RESISTOR-0603"))
    )
    (comp (ref "R50")
      (value "10K")
      (footprint "eagle-import:R0603")
      (libsource (lib "eagle-import") (part "RESISTOR-0603"))
    )
    (comp (ref "R59")
      (value "0.005 1%")
      (footprint "eagle-import:R1206")
      (libsource (lib "eagle-import") (part "RESISTOR-1206"))
    )
    (comp (ref "R60")
      (value "0.005 1%")
      (footprint "eagle-import:R1206")
      (libsource (lib "eagle-import") (part "RESISTOR-1206"))
    )
    (comp (ref "R61")
      (value "0.005 1%")
      (footprint "eagle-import:R1206")
      (libsource (lib "eagle-import") (part "RESISTOR-1206"))
    )
    (comp (ref "R66")
      (value "10K")
      (footprint "eagle-import:R0603")
      (libsource (lib "eagle-import") (part "RESISTOR-0603"))
    )
    (comp (ref "U9")
      (value "INA199A2")
      (footprint "eagle-import:SC70-6L")
      (libsource (lib "eagle-import") (part "INA199"))
    )
    (comp (ref "U10")
      (value "INA199A2")
      (footprint "eagle-import:SC70-6L")
      (libsource (lib "eagle-import") (part "INA199"))
    )
    (comp (ref "U11")
      (value "INA199A2")
      (footprint "eagle-import:SC70-6L")
      (libsource (lib "eagle-import") (part "INA199"))
    )
  )
  (nets
    (net (code "1") (name "+3V3") (class "Default")
      (node (ref "C44") (pin "1") (pinfunction "1_1") (pintype "passive"))
      (node (ref "J1") (pin "9") (pinfunction "1_9") (pintype "passive"))
      (node (ref "J4") (pin "13") (pinfunction "1_13") (pintype "passive"))
      (node (ref "J5") (pin "14") (pinfunction "14_14") (pintype "passive"))
      (node (ref "Q8") (pin "1") (pinfunction "G_1") (pintype "passive"))
      (node (ref "Q9") (pin "1") (pinfunction "G_1") (pintype "passive"))
      (node (ref "R24") (pin "1") (pinfunction "1_1") (pintype "passive"))
      (node (ref "R27") (pin "1") (pinfunction "1_1") (pintype "passive"))
      (node (ref "R30") (pin "1") (pinfunction "1_1") (pintype "passive"))
      (node (ref "R33") (pin "1") (pinfunction "1_1") (pintype "passive"))
      (node (ref "R57") (pin "2") (pinfunction "2_2") (pintype "passive"))
      (node (ref "R58") (pin "2") (pinfunction "2_2") (pintype "passive"))
      (node (ref "U12") (pin "5") (pinfunction "VOUT_5") (pintype "bidirectional"))
    )
    (net (code "2") (name "+3V3_HOMEPLUG") (class "Default")
      (node (ref "C16") (pin "1") (pinfunction "1_1") (pintype "passive"))
      (node (ref "J18") (pin "5") (pinfunction "1_5") (pintype "passive"))
      (node (ref "J18") (pin "6") (pinfunction "1_6") (pintype "passive"))
      (node (ref "J9") (pin "2") (pinfunction "S_2") (pintype "passive"))
      (node (ref "LED8") (pin "A") (pinfunction "A_A") (pintype "passive"))
      (node (ref "U5") (pin "2") (pinfunction "VOUT_2") (pintype "bidirectional"))
      (node (ref "U5") (pin "4") (pinfunction "VOUT_4") (pintype "bidirectional"))
    )
    (net (code "3") (name "+5V") (class "Default")
      (node (ref "C13") (pin "1") (pinfunction "1_1") (pintype "passive"))
      (node (ref "C14") (pin "1") (pinfunction "1_1") (pintype "passive"))
      (node (ref "C15") (pin "1") (pinfunction "1_1") (pintype "passive"))
      (node (ref "C17") (pin "1") (pinfunction "1_1") (pintype "passive"))
      (node (ref "C18") (pin "1") (pinfunction "1_1") (pintype "passive"))
      (node (ref "C22") (pin "1") (pinfunction "1_1") (pintype "passive"))
      (node (ref "C23") (pin "1") (pinfunction "1_1") (pintype "passive"))
      (node (ref "C24") (pin "1") (pinfunction "1_1") (pintype "passive"))
      (node (ref "C25") (pin "1") (pinfunction "1_1") (pintype "passive"))
      (node (ref "C3") (pin "1") (pinfunction "1_1") (pintype "passive"))
      (node (ref "C30") (pin "1") (pinfunction "1_1") (pintype "passive"))
      (node (ref "C31") (pin "1") (pinfunction "1_1") (pintype "passive"))
      (node (ref "C32") (pin "1") (pinfunction "1_1") (pintype "passive"))
      (node (ref "C33") (pin "1") (pinfunction "1_1") (pintype "passive"))
      (node (ref "C34") (pin "+") (pinfunction "+_+") (pintype "passive"))
      (node (ref "C4") (pin "1") (pinfunction "1_1") (pintype "passive"))
      (node (ref "C43") (pin "1") (pinfunction "1_1") (pintype "passive"))
      (node (ref "C7") (pin "1") (pinfunction "1_1") (pintype "passive"))
      (node (ref "J1") (pin "10") (pinfunction "1_10") (pintype "passive"))
      (node (ref "J13") (pin "2") (pinfunction "2_2") (pintype "passive"))
      (node (ref "J2") (pin "1") (pinfunction "1_1") (pintype "passive"))
      (node (ref "J2") (pin "15") (pinfunction "1_15") (pintype "passive"))
      (node (ref "J3") (pin "1") (pinfunction "1_1") (pintype "passive"))
      (node (ref "J3") (pin "15") (pinfunction "1_15") (pintype "passive"))
      (node (ref "J4") (pin "15") (pinfunction "1_15") (pintype "passive"))
      (node (ref "J6") (pin "5") (pinfunction "1_5") (pintype "passive"))
      (node (ref "J6") (pin "6") (pinfunction "1_6") (pintype "passive"))
      (node (ref "L1") (pin "2") (pinfunction "2_2") (pintype "passive"))
      (node (ref "LED4") (pin "A") (pinfunction "A_A") (pintype "passive"))
      (node (ref "R16") (pin "2") (pinfunction "2_2") (pintype "passive"))
      (node (ref "R18") (pin "1") (pinfunction "1_1") (pintype "passive"))
      (node (ref "R20") (pin "1") (pinfunction "1_1") (pintype "passive"))
      (node (ref "R25") (pin "1") (pinfunction "1_1") (pintype "passive"))
      (node (ref "R28") (pin "1") (pinfunction "1_1") (pintype "passive"))
      (node (ref "R31") (pin "1") (pinfunction "1_1") (pintype "passive"))
      (node (ref "R34") (pin "1") (pinfunction "1_1") (pintype "passive"))
      (node (ref "R55") (pin "2") (pinfunction "2_2") (pintype "passive"))
      (node (ref "R56") (pin "2") (pinfunction "2_2") (pintype "passive"))
      (node (ref "SENS1") (pin "3") (pinfunction "V+_3") (pintype "bidirectional"))
      (node (ref "SENS2") (pin "1") (pinfunction "VDD_1") (pintype "bidirectional"))
      (node (ref "U1") (pin "3") (pinfunction "V+_3") (pintype "input"))
      (node (ref "U10") (pin "3") (pinfunction "V+_3") (pintype "input"))
      (node (ref "U11") (pin "3") (pinfunction "V+_3") (pintype "input"))
      (node (ref "U12") (pin "1") (pinfunction "VIN_1") (pintype "bidirectional"))
      (node (ref "U12") (pin "3") (pinfunction "CTRL_3") (pintype "bidirectional"))
      (node (ref "U2") (pin "3") (pinfunction "V+_3") (pintype "input"))
      (node (ref "U3") (pin "3") (pinfunction "V+_3") (pintype "input"))
      (node (ref "U5") (pin "3") (pinfunction "VIN_3") (pintype "input"))
      (node (ref "U6") (pin "10") (pinfunction "VCC_10") (pintype "input"))
      (node (ref "U6") (pin "100") (pinfunction "AVCC_100") (pintype "input"))
      (node (ref "U6") (pin "31") (pinfunction "VCC1_31") (pintype "input"))
      (node (ref "U6") (pin "61") (pinfunction "VCC2_61") (pintype "input"))
      (node (ref "U6") (pin "80") (pinfunction "VCC3_80") (pintype "input"))
      (node (ref "U7") (pin "19") (pinfunction "VCCB_19") (pintype "bidirectional"))
      (node (ref "U9") (pin "3") (pinfunction "V+_3") (pintype "input"))
    )
    (net (code "4") (name "3V3_SCL") (class "Default")
      (node (ref "J1") (pin "11") (pinfunction "1_11") (pintype "passive"))
      (node (ref "J5") (pin "15") (pinfunction "15_15") (pintype "passive"))
      (node (ref "Q8") (pin "2") (pinfunction "S_2") (pintype "passive"))
      (node (ref "R57") (pin "1") (pinfunction "1_1") (pintype "passive"))
    )
    (net (code "5") (name "3V3_SDA") (class "Default")
      (node (ref "J1") (pin "13") (pinfunction "1_13") (pintype "passive"))
      (node (ref "J5") (pin "16") (pinfunction "16_16") (pintype "passive"))
      (node (ref "Q9") (pin "2") (pinfunction "S_2") (pintype "passive"))
      (node (ref "R58") (pin "1") (pinfunction "1_1") (pintype "passive"))
    )
    (net (code "6") (name "ADC0") (class "Default")
      (node (ref "U3") (pin "6") (pinfunction "VOUT_6") (pintype "output"))
      (node (ref "U6") (pin "97") (pinfunction "(ADC0)PF0_97") (pintype "bidirectional"))
    )
    (net (code "7") (name "ADC1") (class "Default")
      (node (ref "C38") (pin "1") (pinfunction "1_1") (pintype "passive"))
      (node (ref "R66") (pin "2") (pinfunction "2_2") (pintype "passive"))
      (node (ref "U6") (pin "96") (pinfunction "(ADC1)PF1_96") (pintype "bidirectional"))
    )
    (net (code "8") (name "ADC2") (class "Default")
      (node (ref "C37") (pin "1") (pinfunction "1_1") (pintype "passive"))
      (node (ref "R50") (pin "2") (pinfunction "2_2") (pintype "passive"))
      (node (ref "U6") (pin "95") (pinfunction "(ADC2)PF2_95") (pintype "bidirectional"))
    )
    (net (code "9") (name "ADC3") (class "Default")
      (node (ref "C36") (pin "1") (pinfunction "1_1") (pintype "passive"))
      (node (ref "R49") (pin "2") (pinfunction "2_2") (pintype "passive"))
      (node (ref "U6") (pin "94") (pinfunction "(ADC3)PF3_94") (pintype "bidirectional"))
    )
    (net (code "10") (name "ADC4") (class "Default")
      (node (ref "C6") (pin "1") (pinfunction "1_1") (pintype "passive"))
      (node (ref "R10") (pin "2") (pinfunction "2_2") (pintype "passive"))
      (node (ref "R11") (pin "1") (pinfunction "1_1") (pintype "passive"))
      (node (ref "U6") (pin "93") (pinfunction "(ADC4/TCK)PF4_93") (pintype "bidirectional"))
    )
    (net (code "11") (name "ADC5") (class "Default")
      (node (ref "U1") (pin "6") (pinfunction "VOUT_6") (pintype "output"))
      (node (ref "U6") (pin "92") (pinfunction "(ADC5/TMS)PF5_92") (pintype "bidirectional"))
    )
    (net (code "12") (name "ADC6") (class "Default")
      (node (ref "U2") (pin "6") (pinfunction "VOUT_6") (pintype "output"))
      (node (ref "U6") (pin "91") (pinfunction "(ADC6/TDO)PF6_91") (pintype "bidirectional"))
    )
    (net (code "13") (name "ADC7") (class "Default")
      (node (ref "C27") (pin "1") (pinfunction "1_1") (pintype "passive"))
      (node (ref "R45") (pin "2") (pinfunction "2_2") (pintype "passive"))
      (node (ref "U6") (pin "90") (pinfunction "(ADC7/TDI)PF7_90") (pintype "bidirectional"))
    )
    (net (code "14") (name "ADC8") (class "Default")
      (node (ref "C26") (pin "1") (pinfunction "1_1") (pintype "passive"))
      (node (ref "R44") (pin "2") (pinfunction "2_2") (pintype "passive"))
      (node (ref "U6") (pin "89") (pinfunction "PK0(ADC8/PCINT16)_89") (pintype "bidirectional"))
    )
    (net (code "15") (name "ADC9") (class "Default")
      (node (ref "J4") (pin "14") (pinfunction "1_14") (pintype "passive"))
      (node (ref "U6") (pin "88") (pinfunction "PK1(ADC9/PCINT17)_88") (pintype "bidirectional"))
    )
    (net (code "16") (name "ADC10") (class "Default")
      (node (ref "J4") (pin "12") (pinfunction "1_12") (pintype "passive"))
      (node (ref "U6") (pin "87") (pinfunction "PK2(ADC10/PCINT18)_87") (pintype "bidirectional"))
    )
    (net (code "17") (name "ADC11") (class "Default")
      (node (ref "J4") (pin "10") (pinfunction "1_10") (pintype "passive"))
      (node (ref "U6") (pin "86") (pinfunction "PK3(ADC11/PCINT19)_86") (pintype "bidirectional"))
    )
    (net (code "18") (name "ADC12") (class "Default")
      (node (ref "J4") (pin "8") (pinfunction "1_8") (pintype "passive"))
      (node (ref "U6") (pin "85") (pinfunction "PK4(ADC12/PCINT20)_85") (pintype "bidirectional"))
    )
    (net (code "19") (name "ADC13") (class "Default")
      (node (ref "J4") (pin "6") (pinfunction "1_6") (pintype "passive"))
      (node (ref "U6") (pin "84") (pinfunction "PK5(ADC13/PCINT21)_84") (pintype "bidirectional"))
    )
    (net (code "20") (name "ADC14") (class "Default")
      (node (ref "J4") (pin "4") (pinfunction "1_4") (pintype "passive"))
      (node (ref "U6") (pin "83") (pinfunction "PK6(ADC14/PCINT22)_83") (pintype "bidirectional"))
    )
    (net (code "21") (name "ADC15") (class "Default")
      (node (ref "J4") (pin "2") (pinfunction "1_2") (pintype "passive"))
      (node (ref "U6") (pin "82") (pinfunction "PK7(ADC15/PCINT23)_82") (pintype "bidirectional"))
    )
    (net (code "22") (name "AREF") (class "Default")
      (node (ref "C21") (pin "1") (pinfunction "1_1") (pintype "passive"))
      (node (ref "J4") (pin "16") (pinfunction "1_16") (pintype "passive"))
      (node (ref "U6") (pin "98") (pinfunction "AREF_98") (pintype "bidirectional"))
    )
    (net (code "23") (name "BAT_1+") (class "Default")
      (node (ref "C1") (pin "1") (pinfunction "1_1") (pintype "passive"))
      (node (ref "D1") (pin "1") (pinfunction "A_1") (pintype "passive"))
      (node (ref "D1") (pin "3") (pinfunction "A_3") (pintype "passive"))
      (node (ref "J5") (pin "5") (pinfunction "5_5") (pintype "passive"))
    )
    (net (code "24") (name "BAT_2+") (class "Default")
      (node (ref "C2") (pin "1") (pinfunction "1_1") (pintype "passive"))
      (node (ref "D2") (pin "1") (pinfunction "A_1") (pintype "passive"))
      (node (ref "D2") (pin "3") (pinfunction "A_3") (pintype "passive"))
      (node (ref "J5") (pin "6") (pinfunction "6_6") (pintype "passive"))
    )
    (net (code "25") (name "BB_3V3") (class "Default")
      (node (ref "C28") (pin "1") (pinfunction "1_1") (pintype "passive"))
      (node (ref "C29") (pin "1") (pinfunction "1_1") (pintype "passive"))
      (node (ref "J6") (pin "3") (pinfunction "1_3") (pintype "passive"))
      (node (ref "J6") (pin "4") (pinfunction "1_4") (pintype "passive"))
      (node (ref "LED3") (pin "A") (pinfunction "A_A") (pintype "passive"))
      (node (ref "R46") (pin "2") (pinfunction "2_2") (pintype "passive"))
      (node (ref "R47") (pin "2") (pinfunction "2_2") (pintype "passive"))
      (node (ref "R51") (pin "2") (pinfunction "2_2") (pintype "passive"))
      (node (ref "R52") (pin "2") (pinfunction "2_2") (pintype "passive"))
      (node (ref "R53") (pin "2") (pinfunction "2_2") (pintype "passive"))
      (node (ref "R54") (pin "2") (pinfunction "2_2") (pintype "passive"))
      (node (ref "R62") (pin "2") (pinfunction "2_2") (pintype "passive"))
      (node (ref "U7") (pin "2") (pinfunction "VCCA_2") (pintype "bidirectional"))
      (node (ref "U8") (pin "8") (pinfunction "VCC_8") (pintype "bidirectional"))
    )
    (net (code "26") (name "BB_P9_11") (class "Default")
      (node (ref "J6") (pin "11") (pinfunction "1_11") (pintype "passive"))
      (node (ref "R46") (pin "1") (pinfunction "1_1") (pintype "passive"))
      (node (ref "U7") (pin "8") (pinfunction "A7_8") (pintype "bidirectional"))
    )
    (net (code "27") (name "BB_P9_12") (class "Default")
      (node (ref "J6") (pin "12") (pinfunction "1_12") (pintype "passive"))
    )
    (net (code "28") (name "BB_P9_13") (class "Default")
      (node (ref "J6") (pin "13") (pinfunction "1_13") (pintype "passive"))
    )
    (net (code "29") (name "BB_P9_14") (class "Default")
      (node (ref "J6") (pin "14") (pinfunction "1_14") (pintype "passive"))
    )
    (net (code "30") (name "BB_P9_15") (class "Default")
      (node (ref "J6") (pin "15") (pinfunction "1_15") (pintype "passive"))
    )
    (net (code "31") (name "BB_P9_16") (class "Default")
      (node (ref "J6") (pin "16") (pinfunction "1_16") (pintype "passive"))
    )
    (net (code "32") (name "BB_P9_17") (class "Default")
      (node (ref "J6") (pin "17") (pinfunction "1_17") (pintype "passive"))
      (node (ref "U7") (pin "4") (pinfunction "A3_4") (pintype "bidirectional"))
    )
    (net (code "33") (name "BB_P9_18") (class "Default")
      (node (ref "J6") (pin "18") (pinfunction "1_18") (pintype "passive"))
      (node (ref "U7") (pin "6") (pinfunction "A5_6") (pintype "bidirectional"))
    )
    (net (code "34") (name "BB_P9_19") (class "Default")
      (node (ref "J6") (pin "19") (pinfunction "1_19") (pintype "passive"))
      (node (ref "R53") (pin "1") (pinfunction "1_1") (pintype "passive"))
      (node (ref "U8") (pin "6") (pinfunction "SCL_6") (pintype "bidirectional"))
    )
    (net (code "35") (name "BB_P9_20") (class "Default")
      (node (ref "J6") (pin "20") (pinfunction "1_20") (pintype "passive"))
      (node (ref "R54") (pin "1") (pinfunction "1_1") (pintype "passive"))
      (node (ref "U8") (pin "5") (pinfunction "SDA_5") (pintype "bidirectional"))
    )
    (net (code "36") (name "BB_P9_21") (class "Default")
      (node (ref "J6") (pin "21") (pinfunction "1_21") (pintype "passive"))
      (node (ref "U7") (pin "7") (pinfunction "A6_7") (pintype "bidirectional"))
    )
    (net (code "37") (name "BB_P9_22") (class "Default")
      (node (ref "J6") (pin "22") (pinfunction "1_22") (pintype "passive"))
      (node (ref "U7") (pin "5") (pinfunction "A4_5") (pintype "bidirectional"))
    )
    (net (code "38") (name "BB_P9_23") (class "Default")
      (node (ref "J6") (pin "23") (pinfunction "1_23") (pintype "passive"))
    )
    (net (code "39") (name "BB_P9_24") (class "Default")
      (node (ref "J6") (pin "24") (pinfunction "1_24") (pintype "passive"))
      (node (ref "R21") (pin "2") (pinfunction "2_2") (pintype "passive"))
      (node (ref "U7") (pin "1") (pinfunction "A1_1") (pintype "bidirectional"))
    )
    (net (code "40") (name "BB_P9_25") (class "Default")
      (node (ref "J6") (pin "25") (pinfunction "1_25") (pintype "passive"))
    )
    (net (code "41") (name "BB_P9_26") (class "Default")
      (node (ref "J6") (pin "26") (pinfunction "1_26") (pintype "passive"))
      (node (ref "U7") (pin "3") (pinfunction "A2_3") (pintype "bidirectional"))
    )
    (net (code "42") (name "BB_P9_27") (class "Default")
      (node (ref "J6") (pin "27") (pinfunction "1_27") (pintype "passive"))
    )
    (net (code "43") (name "BB_P9_28") (class "Default")
      (node (ref "J6") (pin "28") (pinfunction "1_28") (pintype "passive"))
    )
    (net (code "44") (name "BB_P9_29") (class "Default")
      (node (ref "J6") (pin "29") (pinfunction "1_29") (pintype "passive"))
    )
    (net (code "45") (name "BB_P9_30") (class "Default")
      (node (ref "J6") (pin "30") (pinfunction "1_30") (pintype "passive"))
    )
    (net (code "46") (name "BB_P9_31") (class "Default")
      (node (ref "J6") (pin "31") (pinfunction "1_31") (pintype "passive"))
    )
    (net (code "47") (name "BB_P9_32") (class "Default")
      (node (ref "J6") (pin "32") (pinfunction "1_32") (pintype "passive"))
    )
    (net (code "48") (name "BB_P9_33") (class "Default")
      (node (ref "J6") (pin "33") (pinfunction "1_33") (pintype "passive"))
    )
    (net (code "49") (name "BB_P9_34") (class "Default")
      (node (ref "J6") (pin "34") (pinfunction "1_34") (pintype "passive"))
    )
    (net (code "50") (name "BB_P9_35") (class "Default")
      (node (ref "J6") (pin "35") (pinfunction "1_35") (pintype "passive"))
    )
    (net (code "51") (name "BB_P9_36") (class "Default")
      (node (ref "J6") (pin "36") (pinfunction "1_36") (pintype "passive"))
    )
    (net (code "52") (name "BB_P9_37") (class "Default")
      (node (ref "J6") (pin "37") (pinfunction "1_37") (pintype "passive"))
    )
    (net (code "53") (name "BB_P9_38") (class "Default")
      (node (ref "J6") (pin "38") (pinfunction "1_38") (pintype "passive"))
    )
    (net (code "54") (name "BB_P9_39") (class "Default")
      (node (ref "J6") (pin "39") (pinfunction "1_39") (pintype "passive"))
    )
    (net (code "55") (name "BB_P9_40") (class "Default")
      (node (ref "J6") (pin "40") (pinfunction "1_40") (pintype "passive"))
    )
    (net (code "56") (name "BB_P9_41") (class "Default")
      (node (ref "J6") (pin "41") (pinfunction "1_41") (pintype "passive"))
    )
    (net (code "57") (name "BB_P9_42") (class "Default")
      (node (ref "J6") (pin "42") (pinfunction "1_42") (pintype "passive"))
    )
    (net (code "58") (name "BB_PWR_BUT") (class "Default")
      (node (ref "J6") (pin "9") (pinfunction "1_9") (pintype "passive"))
    )
    (net (code "59") (name "BB_SYS_5V") (class "Default")
      (node (ref "J6") (pin "7") (pinfunction "1_7") (pintype "passive"))
      (node (ref "J6") (pin "8") (pinfunction "1_8") (pintype "passive"))
    )
    (net (code "60") (name "BB_SYS_RESET*") (class "Default")
      (node (ref "J6") (pin "10") (pinfunction "1_10") (pintype "passive"))
      (node (ref "R48") (pin "2") (pinfunction "2_2") (pintype "passive"))
    )
    (net (code "61") (name "D0{slash}UART_RX") (class "Default")
      (node (ref "U6") (pin "2") (pinfunction "(RXD0/PCIN8)PE0_2") (pintype "bidirectional"))
      (node (ref "U7") (pin "20") (pinfunction "B1_20") (pintype "bidirectional"))
    )
    (net (code "62") (name "D1{slash}UART_TX") (class "Default")
      (node (ref "R22") (pin "2") (pinfunction "2_2") (pintype "passive"))
      (node (ref "U6") (pin "3") (pinfunction "(TXD0)PE1_3") (pintype "bidirectional"))
      (node (ref "U7") (pin "18") (pinfunction "B2_18") (pintype "bidirectional"))
    )
    (net (code "63") (name "D2") (class "Default")
      (node (ref "J3") (pin "11") (pinfunction "1_11") (pintype "passive"))
      (node (ref "U6") (pin "6") (pinfunction "(OC3B/INT4)PE4_6") (pintype "bidirectional"))
    )
    (net (code "64") (name "D3") (class "Default")
      (node (ref "J3") (pin "9") (pinfunction "1_9") (pintype "passive"))
      (node (ref "U6") (pin "7") (pinfunction "(OC3C/INT5)PE5_7") (pintype "bidirectional"))
    )
    (net (code "65") (name "D4") (class "Default")
      (node (ref "J3") (pin "7") (pinfunction "1_7") (pintype "passive"))
      (node (ref "U6") (pin "1") (pinfunction "(OC0B)PG5_1") (pintype "bidirectional"))
    )
    (net (code "66") (name "D5") (class "Default")
      (node (ref "J3") (pin "5") (pinfunction "1_5") (pintype "passive"))
      (node (ref "U6") (pin "5") (pinfunction "(OC3A/AIN1)PE3_5") (pintype "bidirectional"))
    )
    (net (code "67") (name "D6") (class "Default")
      (node (ref "J20") (pin "P1") (pinfunction "1_P1") (pintype "passive"))
      (node (ref "U6") (pin "15") (pinfunction "PH3(OC4A)_15") (pintype "bidirectional"))
    )
    (net (code "68") (name "D7") (class "Default")
      (node (ref "J20") (pin "P4") (pinfunction "1_P4") (pintype "passive"))
      (node (ref "U6") (pin "16") (pinfunction "PH4(OC4B)_16") (pintype "bidirectional"))
    )
    (net (code "69") (name "D8") (class "Default")
      (node (ref "J20") (pin "P7") (pinfunction "1_P7") (pintype "passive"))
      (node (ref "U6") (pin "17") (pinfunction "PH5(OC4C)_17") (pintype "bidirectional"))
    )
    (net (code "70") (name "D9") (class "Default")
      (node (ref "J21") (pin "P1") (pinfunction "1_P1") (pintype "passive"))
      (node (ref "U6") (pin "18") (pinfunction "PH6(OC2B)_18") (pintype "bidirectional"))
    )
    (net (code "71") (name "D10") (class "Default")
      (node (ref "J21") (pin "P4") (pinfunction "1_P4") (pintype "passive"))
      (node (ref "U6") (pin "23") (pinfunction "(OC2A/PCINT4)PB4_23") (pintype "bidirectional"))
    )
    (net (code "72") (name "D11") (class "Default")
      (node (ref "J21") (pin "P7") (pinfunction "1_P7") (pintype "passive"))
      (node (ref "U6") (pin "24") (pinfunction "(OC1A/PCINT5)PB5_24") (pintype "bidirectional"))
    )
    (net (code "73") (name "D12") (class "Default")
      (node (ref "R39") (pin "1") (pinfunction "1_1") (pintype "passive"))
      (node (ref "U6") (pin "25") (pinfunction "(OC1B/PCINT6)PB6_25") (pintype "bidirectional"))
    )
    (net (code "74") (name "D13") (class "Default")
      (node (ref "R23") (pin "1") (pinfunction "1_1") (pintype "passive"))
      (node (ref "U6") (pin "26") (pinfunction "(OC0A/OC1C/PCINT7)PB7_26") (pintype "bidirectional"))
    )
    (net (code "75") (name "D14") (class "Default")
      (node (ref "J2") (pin "11") (pinfunction "1_11") (pintype "passive"))
      (node (ref "U6") (pin "64") (pinfunction "PJ1(TXD3/PCINT10)_64") (pintype "bidirectional"))
    )
    (net (code "76") (name "D15") (class "Default")
      (node (ref "J2") (pin "9") (pinfunction "1_9") (pintype "passive"))
      (node (ref "U6") (pin "63") (pinfunction "PJ0(RXD3/PCINT9)_63") (pintype "bidirectional"))
    )
    (net (code "77") (name "D16{slash}ESC_POWER_SWITCH") (class "Default")
      (node (ref "R5") (pin "2") (pinfunction "2_2") (pintype "passive"))
      (node (ref "U6") (pin "13") (pinfunction "PH1(TXD2)_13") (pintype "bidirectional"))
    )
    (net (code "78") (name "D17") (class "Default")
      (node (ref "U6") (pin "12") (pinfunction "PH0(RXD2)_12") (pintype "bidirectional"))
    )
    (net (code "79") (name "D18") (class "Default")
      (node (ref "J2") (pin "7") (pinfunction "1_7") (pintype "passive"))
      (node (ref "U6") (pin "46") (pinfunction "(TXD1/INT3)PD3_46") (pintype "bidirectional"))
    )
    (net (code "80") (name "D19") (class "Default")
      (node (ref "J2") (pin "5") (pinfunction "1_5") (pintype "passive"))
      (node (ref "U6") (pin "45") (pinfunction "(RXD1/INT2)PD2_45") (pintype "bidirectional"))
    )
    (net (code "81") (name "D20{slash}5V_SDA") (class "Default")
      (node (ref "J1") (pin "14") (pinfunction "1_14") (pintype "passive"))
      (node (ref "Q9") (pin "3") (pinfunction "D_3") (pintype "passive"))
      (node (ref "R56") (pin "1") (pinfunction "1_1") (pintype "passive"))
      (node (ref "U6") (pin "44") (pinfunction "(SDA/INT1)PD1_44") (pintype "bidirectional"))
    )
    (net (code "82") (name "D21{slash}5V_SCL") (class "Default")
      (node (ref "J1") (pin "12") (pinfunction "1_12") (pintype "passive"))
      (node (ref "Q8") (pin "3") (pinfunction "D_3") (pintype "passive"))
      (node (ref "R55") (pin "1") (pinfunction "1_1") (pintype "passive"))
      (node (ref "U6") (pin "43") (pinfunction "(SCL/INT0)PD0_43") (pintype "bidirectional"))
    )
    (net (code "83") (name "D22") (class "Default")
      (node (ref "J3") (pin "16") (pinfunction "1_16") (pintype "passive"))
      (node (ref "U6") (pin "78") (pinfunction "(AD0)PA0_78") (pintype "bidirectional"))
    )
    (net (code "84") (name "D23") (class "Default")
      (node (ref "J3") (pin "14") (pinfunction "1_14") (pintype "passive"))
      (node (ref "U6") (pin "77") (pinfunction "(AD1)PA1_77") (pintype "bidirectional"))
    )
    (net (code "85") (name "D24") (class "Default")
      (node (ref "J3") (pin "12") (pinfunction "1_12") (pintype "passive"))
      (node (ref "U6") (pin "76") (pinfunction "(AD2)PA2_76") (pintype "bidirectional"))
    )
    (net (code "86") (name "D25") (class "Default")
      (node (ref "J3") (pin "10") (pinfunction "1_10") (pintype "passive"))
      (node (ref "U6") (pin "75") (pinfunction "(AD3)PA3_75") (pintype "bidirectional"))
    )
    (net (code "87") (name "D26") (class "Default")
      (node (ref "J3") (pin "8") (pinfunction "1_8") (pintype "passive"))
      (node (ref "U6") (pin "74") (pinfunction "(AD4)PA4_74") (pintype "bidirectional"))
    )
    (net (code "88") (name "D27") (class "Default")
      (node (ref "J3") (pin "6") (pinfunction "1_6") (pintype "passive"))
      (node (ref "U6") (pin "73") (pinfunction "(AD5)PA5_73") (pintype "bidirectional"))
    )
    (net (code "89") (name "D28") (class "Default")
      (node (ref "J3") (pin "4") (pinfunction "1_4") (pintype "passive"))
      (node (ref "U6") (pin "72") (pinfunction "(AD6)PA6_72") (pintype "bidirectional"))
    )
    (net (code "90") (name "D29") (class "Default")
      (node (ref "J3") (pin "2") (pinfunction "1_2") (pintype "passive"))
      (node (ref "U6") (pin "71") (pinfunction "(AD7)PA7_71") (pintype "bidirectional"))
    )
    (net (code "91") (name "D30") (class "Default")
      (node (ref "J2") (pin "16") (pinfunction "1_16") (pintype "passive"))
      (node (ref "U6") (pin "60") (pinfunction "(A15)PC7_60") (pintype "bidirectional"))
    )
    (net (code "92") (name "D31") (class "Default")
      (node (ref "J2") (pin "14") (pinfunction "1_14") (pintype "passive"))
      (node (ref "U6") (pin "59") (pinfunction "(A14)PC6_59") (pintype "bidirectional"))
    )
    (net (code "93") (name "D32") (class "Default")
      (node (ref "J2") (pin "12") (pinfunction "1_12") (pintype "passive"))
      (node (ref "U6") (pin "58") (pinfunction "(A13)PC5_58") (pintype "bidirectional"))
    )
    (net (code "94") (name "D33") (class "Default")
      (node (ref "J2") (pin "10") (pinfunction "1_10") (pintype "passive"))
      (node (ref "U6") (pin "57") (pinfunction "(A12)PC4_57") (pintype "bidirectional"))
    )
    (net (code "95") (name "D34") (class "Default")
      (node (ref "J2") (pin "8") (pinfunction "1_8") (pintype "passive"))
      (node (ref "U6") (pin "56") (pinfunction "(A11)PC3_56") (pintype "bidirectional"))
    )
    (net (code "96") (name "D35") (class "Default")
      (node (ref "J2") (pin "6") (pinfunction "1_6") (pintype "passive"))
      (node (ref "U6") (pin "55") (pinfunction "(A10)PC2_55") (pintype "bidirectional"))
    )
    (net (code "97") (name "D36") (class "Default")
      (node (ref "J2") (pin "4") (pinfunction "1_4") (pintype "passive"))
      (node (ref "U6") (pin "54") (pinfunction "(A9)PC1_54") (pintype "bidirectional"))
    )
    (net (code "98") (name "D37") (class "Default")
      (node (ref "J2") (pin "2") (pinfunction "1_2") (pintype "passive"))
      (node (ref "U6") (pin "53") (pinfunction "(A8)PC0_53") (pintype "bidirectional"))
    )
    (net (code "99") (name "D38") (class "Default")
      (node (ref "U6") (pin "50") (pinfunction "(T0)PD7_50") (pintype "bidirectional"))
    )
    (net (code "100") (name "D39") (class "Default")
      (node (ref "U6") (pin "70") (pinfunction "(ALE)PG2_70") (pintype "bidirectional"))
    )
    (net (code "101") (name "D40") (class "Default")
      (node (ref "U6") (pin "52") (pinfunction "(RD)PG1_52") (pintype "bidirectional"))
    )
    (net (code "102") (name "D41") (class "Default")
      (node (ref "U6") (pin "51") (pinfunction "(WR)PG0_51") (pintype "bidirectional"))
    )
    (net (code "103") (name "D42") (class "Default")
      (node (ref "U6") (pin "42") (pinfunction "PL7_42") (pintype "bidirectional"))
    )
    (net (code "104") (name "D43") (class "Default")
      (node (ref "U6") (pin "41") (pinfunction "PL6_41") (pintype "bidirectional"))
    )
    (net (code "105") (name "D44") (class "Default")
      (node (ref "R36") (pin "1") (pinfunction "1_1") (pintype "passive"))
      (node (ref "U6") (pin "40") (pinfunction "PL5(OC5C)_40") (pintype "bidirectional"))
    )
    (net (code "106") (name "D45") (class "Default")
      (node (ref "R37") (pin "1") (pinfunction "1_1") (pintype "passive"))
      (node (ref "U6") (pin "39") (pinfunction "PL4(OC5B)_39") (pintype "bidirectional"))
    )
    (net (code "107") (name "D46") (class "Default")
      (node (ref "R38") (pin "1") (pinfunction "1_1") (pintype "passive"))
      (node (ref "U6") (pin "38") (pinfunction "PL3(OC5A)_38") (pintype "bidirectional"))
    )
    (net (code "108") (name "D47") (class "Default")
      (node (ref "U6") (pin "37") (pinfunction "PL2(T5)_37") (pintype "bidirectional"))
    )
    (net (code "109") (name "D48") (class "Default")
      (node (ref "U6") (pin "36") (pinfunction "PL1(ICP5)_36") (pintype "bidirectional"))
    )
    (net (code "110") (name "D49") (class "Default")
      (node (ref "R19") (pin "1") (pinfunction "1_1") (pintype "passive"))
      (node (ref "U6") (pin "35") (pinfunction "PL0(ICP4)_35") (pintype "bidirectional"))
    )
    (net (code "111") (name "D50{slash}SPI_MISO") (class "Default")
      (node (ref "J13") (pin "1") (pinfunction "1_1") (pintype "passive"))
      (node (ref "U6") (pin "22") (pinfunction "(MISO/PCINT3)PB3_22") (pintype "bidirectional"))
      (node (ref "U7") (pin "14") (pinfunction "B6_14") (pintype "bidirectional"))
    )
    (net (code "112") (name "D51{slash}SPI_MOSI") (class "Default")
      (node (ref "J13") (pin "4") (pinfunction "4_4") (pintype "passive"))
      (node (ref "U6") (pin "21") (pinfunction "(MOSI/PCINT2)PB2_21") (pintype "bidirectional"))
      (node (ref "U7") (pin "15") (pinfunction "B5_15") (pintype "bidirectional"))
    )
    (net (code "113") (name "D52{slash}SPI_SCK") (class "Default")
      (node (ref "J13") (pin "3") (pinfunction "3_3") (pintype "passive"))
      (node (ref "U6") (pin "20") (pinfunction "(SCK/PCINT1)PB1_20") (pintype "bidirectional"))
      (node (ref "U7") (pin "16") (pinfunction "B4_16") (pintype "bidirectional"))
    )
    (net (code "114") (name "D53{slash}SPI_SS") (class "Default")
      (node (ref "U6") (pin "19") (pinfunction "(SS/PCINT0)PB0_19") (pintype "bidirectional"))
      (node (ref "U7") (pin "17") (pinfunction "B3_17") (pintype "bidirectional"))
    )
    (net (code "115") (name "ESC_1A") (class "Default")
      (node (ref "J14") (pin "A1") (pinfunction "S_A1") (pintype "passive"))
      (node (ref "J14") (pin "A2") (pinfunction "S_A2") (pintype "passive"))
      (node (ref "J5") (pin "1") (pinfunction "1_1") (pintype "passive"))
    )
    (net (code "116") (name "ESC_1B") (class "Default")
      (node (ref "J14") (pin "B1") (pinfunction "S_B1") (pintype "passive"))
      (node (ref "J14") (pin "B2") (pinfunction "S_B2") (pintype "passive"))
      (node (ref "J5") (pin "2") (pinfunction "2_2") (pintype "passive"))
    )
    (net (code "117") (name "ESC_1C") (class "Default")
      (node (ref "J14") (pin "C1") (pinfunction "S_C1") (pintype "passive"))
      (node (ref "J14") (pin "C2") (pinfunction "S_C2") (pintype "passive"))
      (node (ref "J5") (pin "3") (pinfunction "3_3") (pintype "passive"))
    )
    (net (code "118") (name "ESC_2A") (class "Default")
      (node (ref "J15") (pin "A1") (pinfunction "S_A1") (pintype "passive"))
      (node (ref "J15") (pin "A2") (pinfunction "S_A2") (pintype "passive"))
      (node (ref "J5") (pin "8") (pinfunction "8_8") (pintype "passive"))
    )
    (net (code "119") (name "ESC_2B") (class "Default")
      (node (ref "J15") (pin "B1") (pinfunction "S_B1") (pintype "passive"))
      (node (ref "J15") (pin "B2") (pinfunction "S_B2") (pintype "passive"))
      (node (ref "J5") (pin "9") (pinfunction "9_9") (pintype "passive"))
    )
    (net (code "120") (name "ESC_2C") (class "Default")
      (node (ref "J15") (pin "C1") (pinfunction "S_C1") (pintype "passive"))
      (node (ref "J15") (pin "C2") (pinfunction "S_C2") (pintype "passive"))
      (node (ref "J5") (pin "10") (pinfunction "10_10") (pintype "passive"))
    )
    (net (code "121") (name "ESC_3A") (class "Default")
      (node (ref "J16") (pin "A1") (pinfunction "S_A1") (pintype "passive"))
      (node (ref "J16") (pin "A2") (pinfunction "S_A2") (pintype "passive"))
      (node (ref "J5") (pin "11") (pinfunction "11_11") (pintype "passive"))
    )
    (net (code "122") (name "ESC_3B") (class "Default")
      (node (ref "J16") (pin "B1") (pinfunction "S_B1") (pintype "passive"))
      (node (ref "J16") (pin "B2") (pinfunction "S_B2") (pintype "passive"))
      (node (ref "J5") (pin "12") (pinfunction "12_12") (pintype "passive"))
    )
    (net (code "123") (name "ESC_3C") (class "Default")
      (node (ref "J16") (pin "C1") (pinfunction "S_C1") (pintype "passive"))
      (node (ref "J16") (pin "C2") (pinfunction "S_C2") (pintype "passive"))
      (node (ref "J5") (pin "13") (pinfunction "13_13") (pintype "passive"))
    )
    (net (code "124") (name "ESC_POWER") (class "Default")
      (node (ref "Q3") (pin "5") (pinfunction "D_5") (pintype "passive"))
      (node (ref "Q3") (pin "6") (pinfunction "D_6") (pintype "passive"))
      (node (ref "Q3") (pin "7") (pinfunction "D_7") (pintype "passive"))
      (node (ref "Q3") (pin "8") (pinfunction "D_8") (pintype "passive"))
      (node (ref "R59") (pin "1") (pinfunction "1_1") (pintype "passive"))
      (node (ref "R60") (pin "1") (pinfunction "1_1") (pintype "passive"))
      (node (ref "R61") (pin "1") (pinfunction "1_1") (pintype "passive"))
      (node (ref "U10") (pin "4") (pinfunction "IN+_4") (pintype "input"))
      (node (ref "U11") (pin "4") (pinfunction "IN+_4") (pintype "input"))
      (node (ref "U9") (pin "4") (pinfunction "IN+_4") (pintype "input"))
    )
    (net (code "125") (name "GND") (class "Default")
      (node (ref "C1") (pin "2") (pinfunction "2_2") (pintype "passive"))
      (node (ref "C11") (pin "2") (pinfunction "2_2") (pintype "passive"))
      (node (ref "C13") (pin "2") (pinfunction "2_2") (pintype "passive"))
      (node (ref "C14") (pin "2") (pinfunction "2_2") (pintype "passive"))
      (node (ref "C15") (pin "2") (pinfunction "2_2") (pintype "passive"))
      (node (ref "C16") (pin "2") (pinfunction "2_2") (pintype "passive"))
      (node (ref "C17") (pin "2") (pinfunction "2_2") (pintype "passive"))
      (node (ref "C18") (pin "2") (pinfunction "2_2") (pintype "passive"))
      (node (ref "C19") (pin "2") (pinfunction "2_2") (pintype "passive"))
      (node (ref "C2") (pin "2") (pinfunction "2_2") (pintype "passive"))
      (node (ref "C20") (pin "2") (pinfunction "2_2") (pintype "passive"))
      (node (ref "C21") (pin "2") (pinfunction "2_2") (pintype "passive"))
      (node (ref "C22") (pin "2") (pinfunction "2_2") (pintype "passive"))
      (node (ref "C23") (pin "2") (pinfunction "2_2") (pintype "passive"))
      (node (ref "C24") (pin "2") (pinfunction "2_2") (pintype "passive"))
      (node (ref "C25") (pin "2") (pinfunction "2_2") (pintype "passive"))
      (node (ref "C26") (pin "2") (pinfunction "2_2") (pintype "passive"))
      (node (ref "C27") (pin "2") (pinfunction "2_2") (pintype "passive"))
      (node (ref "C28") (pin "2") (pinfunction "2_2") (pintype "passive"))
      (node (ref "C29") (pin "2") (pinfunction "2_2") (pintype "passive"))
      (node (ref "C3") (pin "2") (pinfunction "2_2") (pintype "passive"))
      (node (ref "C30") (pin "2") (pinfunction "2_2") (pintype "passive"))
      (node (ref "C31") (pin "2") (pinfunction "2_2") (pintype "passive"))
      (node (ref "C32") (pin "2") (pinfunction "2_2") (pintype "passive"))
      (node (ref "C33") (pin "2") (pinfunction "2_2") (pintype "passive"))
      (node (ref "C34") (pin "-") (pinfunction "-_-") (pintype "passive"))
      (node (ref "C35") (pin "2") (pinfunction "2_2") (pintype "passive"))
      (node (ref "C36") (pin "2") (pinfunction "2_2") (pintype "passive"))
      (node (ref "C37") (pin "2") (pinfunction "2_2") (pintype "passive"))
      (node (ref "C38") (pin "2") (pinfunction "2_2") (pintype "passive"))
      (node (ref "C39") (pin "-") (pinfunction "-_-") (pintype "passive"))
      (node (ref "C4") (pin "2") (pinfunction "2_2") (pintype "passive"))
      (node (ref "C40") (pin "-") (pinfunction "-_-") (pintype "passive"))
      (node (ref "C41") (pin "-") (pinfunction "-_-") (pintype "passive"))
      (node (ref "C43") (pin "2") (pinfunction "2_2") (pintype "passive"))
      (node (ref "C44") (pin "2") (pinfunction "2_2") (pintype "passive"))
      (node (ref "C6") (pin "2") (pinfunction "2_2") (pintype "passive"))
      (node (ref "C7") (pin "2") (pinfunction "2_2") (pintype "passive"))
      (node (ref "C8") (pin "2") (pinfunction "2_2") (pintype "passive"))
      (node (ref "C9") (pin "2") (pinfunction "2_2") (pintype "passive"))
      (node (ref "D3") (pin "A") (pinfunction "A_A") (pintype "passive"))
      (node (ref "D6") (pin "A") (pinfunction "A_A") (pintype "passive"))
      (node (ref "J1") (pin "15") (pinfunction "1_15") (pintype "passive"))
      (node (ref "J1") (pin "16") (pinfunction "1_16") (pintype "passive"))
      (node (ref "J11") (pin "2") (pinfunction "S_2") (pintype "passive"))
      (node (ref "J12") (pin "2") (pinfunction "S_2") (pintype "passive"))
      (node (ref "J13") (pin "6") (pinfunction "6_6") (pintype "passive"))
      (node (ref "J14") (pin "GND1") (pinfunction "S_GND1") (pintype "passive"))
      (node (ref "J14") (pin "GND2") (pinfunction "S_GND2") (pintype "passive"))
      (node (ref "J15") (pin "GND1") (pinfunction "S_GND1") (pintype "passive"))
      (node (ref "J15") (pin "GND2") (pinfunction "S_GND2") (pintype "passive"))
      (node (ref "J16") (pin "GND1") (pinfunction "S_GND1") (pintype "passive"))
      (node (ref "J16") (pin "GND2") (pinfunction "S_GND2") (pintype "passive"))
      (node (ref "J17") (pin "2") (pinfunction "S_2") (pintype "passive"))
      (node (ref "J18") (pin "1") (pinfunction "1_1") (pintype "passive"))
      (node (ref "J2") (pin "13") (pinfunction "1_13") (pintype "passive"))
      (node (ref "J2") (pin "3") (pinfunction "1_3") (pintype "passive"))
      (node (ref "J20") (pin "P3") (pinfunction "1_P3") (pintype "passive"))
      (node (ref "J20") (pin "P6") (pinfunction "1_P6") (pintype "passive"))
      (node (ref "J20") (pin "P9") (pinfunction "1_P9") (pintype "passive"))
      (node (ref "J21") (pin "P3") (pinfunction "1_P3") (pintype "passive"))
      (node (ref "J21") (pin "P6") (pinfunction "1_P6") (pintype "passive"))
      (node (ref "J21") (pin "P9") (pinfunction "1_P9") (pintype "passive"))
      (node (ref "J3") (pin "13") (pinfunction "1_13") (pintype "passive"))
      (node (ref "J3") (pin "3") (pinfunction "1_3") (pintype "passive"))
      (node (ref "J4") (pin "1") (pinfunction "1_1") (pintype "passive"))
      (node (ref "J4") (pin "11") (pinfunction "1_11") (pintype "passive"))
      (node (ref "J4") (pin "3") (pinfunction "1_3") (pintype "passive"))
      (node (ref "J4") (pin "5") (pinfunction "1_5") (pintype "passive"))
      (node (ref "J4") (pin "7") (pinfunction "1_7") (pintype "passive"))
      (node (ref "J4") (pin "9") (pinfunction "1_9") (pintype "passive"))
      (node (ref "J5") (pin "17") (pinfunction "17_17") (pintype "passive"))
      (node (ref "J5") (pin "4") (pinfunction "4_4") (pintype "passive"))
      (node (ref "J5") (pin "7") (pinfunction "7_7") (pintype "passive"))
      (node (ref "J6") (pin "1") (pinfunction "1_1") (pintype "passive"))
      (node (ref "J6") (pin "2") (pinfunction "1_2") (pintype "passive"))
      (node (ref "J6") (pin "43") (pinfunction "1_43") (pintype "passive"))
      (node (ref "J6") (pin "44") (pinfunction "1_44") (pintype "passive"))
      (node (ref "J6") (pin "45") (pinfunction "1_45") (pintype "passive"))
      (node (ref "J6") (pin "46") (pinfunction "1_46") (pintype "passive"))
      (node (ref "J7") (pin "2") (pinfunction "S_2") (pintype "passive"))
      (node (ref "J9") (pin "1") (pinfunction "S_1") (pintype "passive"))
      (node (ref "J9") (pin "3") (pinfunction "S_3") (pintype "passive"))
      (node (ref "LED1") (pin "C") (pinfunction "C_C") (pintype "passive"))
      (node (ref "LED2") (pin "C") (pinfunction "C_C") (pintype "passive"))
      (node (ref "LED5") (pin "C") (pinfunction "C_C") (pintype "passive"))
      (node (ref "LED6") (pin "C") (pinfunction "C_C") (pintype "passive"))
      (node (ref "LED7") (pin "C") (pinfunction "C_C") (pintype "passive"))
      (node (ref "OC1") (pin "3") (pinfunction "E_3") (pintype "passive"))
      (node (ref "Q2") (pin "2") (pinfunction "S_2") (pintype "passive"))
      (node (ref "Q4") (pin "2") (pinfunction "S_2") (pintype "passive"))
      (node (ref "Q5") (pin "2") (pinfunction "S_2") (pintype "passive"))
      (node (ref "Q6") (pin "2") (pinfunction "S_2") (pintype "passive"))
      (node (ref "Q7") (pin "2") (pinfunction "S_2") (pintype "passive"))
      (node (ref "R11") (pin "2") (pinfunction "2_2") (pintype "passive"))
      (node (ref "R14") (pin "1") (pinfunction "1_1") (pintype "passive"))
      (node (ref "R17") (pin "1") (pinfunction "1_1") (pintype "passive"))
      (node (ref "R40") (pin "1") (pinfunction "1_1") (pintype "passive"))
      (node (ref "R41") (pin "1") (pinfunction "1_1") (pintype "passive"))
      (node (ref "R42") (pin "1") (pinfunction "1_1") (pintype "passive"))
      (node (ref "R43") (pin "1") (pinfunction "1_1") (pintype "passive"))
      (node (ref "R67") (pin "1") (pinfunction "1_1") (pintype "passive"))
      (node (ref "R7") (pin "2") (pinfunction "2_2") (pintype "passive"))
      (node (ref "SENS1") (pin "1") (pinfunction "GND_1") (pintype "bidirectional"))
      (node (ref "SENS1") (pin "PAD") (pinfunction "PAD_PAD") (pintype "bidirectional"))
      (node (ref "SENS2") (pin "3") (pinfunction "GND_3") (pintype "bidirectional"))
      (node (ref "TP2") (pin "1") (pinfunction "P_1") (pintype "passive"))
      (node (ref "TP3") (pin "1") (pinfunction "P_1") (pintype "passive"))
      (node (ref "U1") (pin "1") (pinfunction "REF_1") (pintype "input"))
      (node (ref "U1") (pin "2") (pinfunction "GND_2") (pintype "input"))
      (node (ref "U10") (pin "1") (pinfunction "REF_1") (pintype "input"))
      (node (ref "U10") (pin "2") (pinfunction "GND_2") (pintype "input"))
      (node (ref "U11") (pin "1") (pinfunction "REF_1") (pintype "input"))
      (node (ref "U11") (pin "2") (pinfunction "GND_2") (pintype "input"))
      (node (ref "U12") (pin "2") (pinfunction "GND_2") (pintype "bidirectional"))
      (node (ref "U2") (pin "1") (pinfunction "REF_1") (pintype "input"))
      (node (ref "U2") (pin "2") (pinfunction "GND_2") (pintype "input"))
      (node (ref "U3") (pin "1") (pinfunction "REF_1") (pintype "input"))
      (node (ref "U3") (pin "2") (pinfunction "GND_2") (pintype "input"))
      (node (ref "U4") (pin "4") (pinfunction "GND_4") (pintype "bidirectional"))
      (node (ref "U4") (pin "PAD") (pinfunction "GNDPAD_PAD") (pintype "bidirectional"))
      (node (ref "U5") (pin "1") (pinfunction "GND_1") (pintype "power_in"))
      (node (ref "U6") (pin "11") (pinfunction "GND_11") (pintype "input"))
      (node (ref "U6") (pin "32") (pinfunction "GND1_32") (pintype "input"))
      (node (ref "U6") (pin "62") (pinfunction "GND2_62") (pintype "input"))
      (node (ref "U6") (pin "81") (pinfunction "GND3_81") (pintype "input"))
      (node (ref "U6") (pin "99") (pinfunction "AGND_99") (pintype "input"))
      (node (ref "U7") (pin "11") (pinfunction "GND_11") (pintype "bidirectional"))
      (node (ref "U8") (pin "1") (pinfunction "A0_1") (pintype "input"))
      (node (ref "U8") (pin "2") (pinfunction "A1_2") (pintype "input"))
      (node (ref "U8") (pin "4") (pinfunction "VSS_4") (pintype "bidirectional"))
      (node (ref "U9") (pin "1") (pinfunction "REF_1") (pintype "input"))
      (node (ref "U9") (pin "2") (pinfunction "GND_2") (pintype "input"))
    )
    (net (code "126") (name "Net-(C5-Pad1)") (class "Default")
      (node (ref "C5") (pin "1") (pinfunction "1_1") (pintype "passive"))
      (node (ref "FB1") (pin "2") (pinfunction "2_2") (pintype "passive"))
      (node (ref "R3") (pin "2") (pinfunction "2_2") (pintype "passive"))
    )
    (net (code "127") (name "Net-(C10-Pad2)") (class "Default")
      (node (ref "C10") (pin "2") (pinfunction "2_2") (pintype "passive"))
      (node (ref "R14") (pin "2") (pinfunction "2_2") (pintype "passive"))
    )
    (net (code "128") (name "Net-(D1-C)") (class "Default")
      (node (ref "D1") (pin "4") (pinfunction "C_4") (pintype "passive"))
      (node (ref "R1") (pin "1") (pinfunction "1_1") (pintype "passive"))
      (node (ref "U2") (pin "4") (pinfunction "IN+_4") (pintype "input"))
    )
    (net (code "129") (name "Net-(D2-C)") (class "Default")
      (node (ref "D2") (pin "4") (pinfunction "C_4") (pintype "passive"))
      (node (ref "R2") (pin "1") (pinfunction "1_1") (pintype "passive"))
      (node (ref "U1") (pin "4") (pinfunction "IN+_4") (pintype "input"))
    )
    (net (code "130") (name "Net-(J11A-S)") (class "Default")
      (node (ref "C42") (pin "1") (pinfunction "1_1") (pintype "passive"))
      (node (ref "D3") (pin "C") (pinfunction "C_C") (pintype "passive"))
      (node (ref "D4") (pin "C") (pinfunction "C_C") (pintype "passive"))
      (node (ref "D5") (pin "C") (pinfunction "C_C") (pintype "passive"))
      (node (ref "J11") (pin "1") (pinfunction "S_1") (pintype "passive"))
      (node (ref "Q1") (pin "1") (pinfunction "S_1") (pintype "passive"))
      (node (ref "Q1") (pin "2") (pinfunction "S_2") (pintype "passive"))
      (node (ref "Q1") (pin "3") (pinfunction "S_3") (pintype "passive"))
      (node (ref "Q3") (pin "1") (pinfunction "S_1") (pintype "passive"))
      (node (ref "Q3") (pin "2") (pinfunction "S_2") (pintype "passive"))
      (node (ref "Q3") (pin "3") (pinfunction "S_3") (pintype "passive"))
      (node (ref "R1") (pin "2") (pinfunction "2_2") (pintype "passive"))
      (node (ref "R2") (pin "2") (pinfunction "2_2") (pintype "passive"))
      (node (ref "R4") (pin "2") (pinfunction "2_2") (pintype "passive"))
      (node (ref "R6") (pin "2") (pinfunction "2_2") (pintype "passive"))
      (node (ref "U1") (pin "5") (pinfunction "IN-_5") (pintype "input"))
      (node (ref "U2") (pin "5") (pinfunction "IN-_5") (pintype "input"))
    )
    (net (code "131") (name "Net-(J12A-S)") (class "Default")
      (node (ref "C35") (pin "1") (pinfunction "1_1") (pintype "passive"))
      (node (ref "J12") (pin "1") (pinfunction "S_1") (pintype "passive"))
      (node (ref "OC1") (pin "4") (pinfunction "C_4") (pintype "passive"))
      (node (ref "R8") (pin "1") (pinfunction "1_1") (pintype "passive"))
    )
    (net (code "132") (name "Net-(J17A-S)") (class "Default")
      (node (ref "J17") (pin "1") (pinfunction "S_1") (pintype "passive"))
      (node (ref "Q2") (pin "3") (pinfunction "D_3") (pintype "passive"))
      (node (ref "R9") (pin "1") (pinfunction "1_1") (pintype "passive"))
    )
    (net (code "133") (name "Net-(J18B-1)") (class "Default")
      (node (ref "J18") (pin "2") (pinfunction "1_2") (pintype "passive"))
      (node (ref "R65") (pin "2") (pinfunction "2_2") (pintype "passive"))
    )
    (net (code "134") (name "Net-(J18C-1)") (class "Default")
      (node (ref "J18") (pin "3") (pinfunction "1_3") (pintype "passive"))
      (node (ref "R63") (pin "2") (pinfunction "2_2") (pintype "passive"))
    )
    (net (code "135") (name "Net-(J18D-1)") (class "Default")
      (node (ref "J18") (pin "4") (pinfunction "1_4") (pintype "passive"))
      (node (ref "R64") (pin "2") (pinfunction "2_2") (pintype "passive"))
    )
    (net (code "136") (name "Net-(J20B-1)") (class "Default")
      (node (ref "J20") (pin "P2") (pinfunction "1_P2") (pintype "passive"))
      (node (ref "J20") (pin "P5") (pinfunction "1_P5") (pintype "passive"))
      (node (ref "J20") (pin "P8") (pinfunction "1_P8") (pintype "passive"))
      (node (ref "J21") (pin "P2") (pinfunction "1_P2") (pintype "passive"))
      (node (ref "J21") (pin "P5") (pinfunction "1_P5") (pintype "passive"))
      (node (ref "J21") (pin "P8") (pinfunction "1_P8") (pintype "passive"))
      (node (ref "J7") (pin "1") (pinfunction "S_1") (pintype "passive"))
    )
    (net (code "137") (name "Net-(LED1-PadA)") (class "Default")
      (node (ref "LED1") (pin "A") (pinfunction "A_A") (pintype "passive"))
      (node (ref "R18") (pin "2") (pinfunction "2_2") (pintype "passive"))
    )
    (net (code "138") (name "Net-(LED2-PadA)") (class "Default")
      (node (ref "LED2") (pin "A") (pinfunction "A_A") (pintype "passive"))
      (node (ref "R19") (pin "2") (pinfunction "2_2") (pintype "passive"))
    )
    (net (code "139") (name "Net-(LED3-PadC)") (class "Default")
      (node (ref "LED3") (pin "C") (pinfunction "C_C") (pintype "passive"))
      (node (ref "R21") (pin "1") (pinfunction "1_1") (pintype "passive"))
    )
    (net (code "140") (name "Net-(LED4-PadC)") (class "Default")
      (node (ref "LED4") (pin "C") (pinfunction "C_C") (pintype "passive"))
      (node (ref "R22") (pin "1") (pinfunction "1_1") (pintype "passive"))
    )
    (net (code "141") (name "Net-(LED5-PadA)") (class "Default")
      (node (ref "LED5") (pin "A") (pinfunction "A_A") (pintype "passive"))
      (node (ref "R23") (pin "2") (pinfunction "2_2") (pintype "passive"))
    )
    (net (code "142") (name "Net-(LED6-PadA)") (class "Default")
      (node (ref "LED6") (pin "A") (pinfunction "A_A") (pintype "passive"))
      (node (ref "R63") (pin "1") (pinfunction "1_1") (pintype "passive"))
    )
    (net (code "143") (name "Net-(LED7-PadA)") (class "Default")
      (node (ref "LED7") (pin "A") (pinfunction "A_A") (pintype "passive"))
      (node (ref "R64") (pin "1") (pinfunction "1_1") (pintype "passive"))
    )
    (net (code "144") (name "Net-(LED8-PadC)") (class "Default")
      (node (ref "LED8") (pin "C") (pinfunction "C_C") (pintype "passive"))
      (node (ref "R65") (pin "1") (pinfunction "1_1") (pintype "passive"))
    )
    (net (code "145") (name "Net-(OC1-IN-A)") (class "Default")
      (node (ref "OC1") (pin "1") (pinfunction "IN-A_1") (pintype "passive"))
      (node (ref "R3") (pin "1") (pinfunction "1_1") (pintype "passive"))
    )
    (net (code "146") (name "Net-(Q1-G)") (class "Default")
      (node (ref "D4") (pin "A") (pinfunction "A_A") (pintype "passive"))
      (node (ref "Q1") (pin "4") (pinfunction "G_4") (pintype "passive"))
      (node (ref "R4") (pin "1") (pinfunction "1_1") (pintype "passive"))
      (node (ref "R8") (pin "2") (pinfunction "2_2") (pintype "passive"))
    )
    (net (code "147") (name "Net-(Q2-G)") (class "Default")
      (node (ref "Q2") (pin "1") (pinfunction "G_1") (pintype "passive"))
      (node (ref "R5") (pin "1") (pinfunction "1_1") (pintype "passive"))
      (node (ref "R7") (pin "1") (pinfunction "1_1") (pintype "passive"))
    )
    (net (code "148") (name "Net-(Q3-G)") (class "Default")
      (node (ref "C42") (pin "2") (pinfunction "2_2") (pintype "passive"))
      (node (ref "D5") (pin "A") (pinfunction "A_A") (pintype "passive"))
      (node (ref "Q3") (pin "4") (pinfunction "G_4") (pintype "passive"))
      (node (ref "R6") (pin "1") (pinfunction "1_1") (pintype "passive"))
      (node (ref "R9") (pin "2") (pinfunction "2_2") (pintype "passive"))
    )
    (net (code "149") (name "Net-(Q4-G)") (class "Default")
      (node (ref "Q4") (pin "1") (pinfunction "G_1") (pintype "passive"))
      (node (ref "R36") (pin "2") (pinfunction "2_2") (pintype "passive"))
      (node (ref "R40") (pin "2") (pinfunction "2_2") (pintype "passive"))
    )
    (net (code "150") (name "Net-(Q5-G)") (class "Default")
      (node (ref "Q5") (pin "1") (pinfunction "G_1") (pintype "passive"))
      (node (ref "R37") (pin "2") (pinfunction "2_2") (pintype "passive"))
      (node (ref "R41") (pin "2") (pinfunction "2_2") (pintype "passive"))
    )
    (net (code "151") (name "Net-(Q6-G)") (class "Default")
      (node (ref "Q6") (pin "1") (pinfunction "G_1") (pintype "passive"))
      (node (ref "R38") (pin "2") (pinfunction "2_2") (pintype "passive"))
      (node (ref "R42") (pin "2") (pinfunction "2_2") (pintype "passive"))
    )
    (net (code "152") (name "Net-(Q7-G)") (class "Default")
      (node (ref "Q7") (pin "1") (pinfunction "G_1") (pintype "passive"))
      (node (ref "R39") (pin "2") (pinfunction "2_2") (pintype "passive"))
      (node (ref "R43") (pin "2") (pinfunction "2_2") (pintype "passive"))
    )
    (net (code "153") (name "Net-(SENS1-OUT)") (class "Default")
      (node (ref "R45") (pin "1") (pinfunction "1_1") (pintype "passive"))
      (node (ref "SENS1") (pin "2") (pinfunction "OUT_2") (pintype "output"))
    )
    (net (code "154") (name "Net-(SENS2-VOUT)") (class "Default")
      (node (ref "R44") (pin "1") (pinfunction "1_1") (pintype "passive"))
      (node (ref "SENS2") (pin "2") (pinfunction "VOUT_2") (pintype "output"))
    )
    (net (code "155") (name "Net-(TP20-P)") (class "Default")
      (node (ref "J5") (pin "20") (pinfunction "20_20") (pintype "passive"))
      (node (ref "TP20") (pin "1") (pinfunction "P_1") (pintype "passive"))
    )
    (net (code "156") (name "Net-(TP21-P)") (class "Default")
      (node (ref "J5") (pin "21") (pinfunction "21_21") (pintype "passive"))
      (node (ref "TP21") (pin "1") (pinfunction "P_1") (pintype "passive"))
    )
    (net (code "157") (name "Net-(TP22-P)") (class "Default")
      (node (ref "J5") (pin "22") (pinfunction "22_22") (pintype "passive"))
      (node (ref "TP22") (pin "1") (pinfunction "P_1") (pintype "passive"))
    )
    (net (code "158") (name "Net-(TP23-P)") (class "Default")
      (node (ref "J5") (pin "23") (pinfunction "23_23") (pintype "passive"))
      (node (ref "TP23") (pin "1") (pinfunction "P_1") (pintype "passive"))
    )
    (net (code "159") (name "Net-(TP24-P)") (class "Default")
      (node (ref "J5") (pin "24") (pinfunction "24_24") (pintype "passive"))
      (node (ref "TP24") (pin "1") (pinfunction "P_1") (pintype "passive"))
    )
    (net (code "160") (name "Net-(TP25-P)") (class "Default")
      (node (ref "J5") (pin "25") (pinfunction "25_25") (pintype "passive"))
      (node (ref "TP25") (pin "1") (pinfunction "P_1") (pintype "passive"))
    )
    (net (code "161") (name "Net-(U3-IN+)") (class "Default")
      (node (ref "Q1") (pin "5") (pinfunction "D_5") (pintype "passive"))
      (node (ref "Q1") (pin "6") (pinfunction "D_6") (pintype "passive"))
      (node (ref "Q1") (pin "7") (pinfunction "D_7") (pintype "passive"))
      (node (ref "Q1") (pin "8") (pinfunction "D_8") (pintype "passive"))
      (node (ref "R10") (pin "1") (pinfunction "1_1") (pintype "passive"))
      (node (ref "R12") (pin "1") (pinfunction "1_1") (pintype "passive"))
      (node (ref "U3") (pin "4") (pinfunction "IN+_4") (pintype "input"))
    )
    (net (code "162") (name "Net-(U4-BOOT)") (class "Default")
      (node (ref "C12") (pin "1") (pinfunction "1_1") (pintype "passive"))
      (node (ref "U4") (pin "1") (pinfunction "BOOT_1") (pintype "bidirectional"))
    )
    (net (code "163") (name "Net-(U4-COMP)") (class "Default")
      (node (ref "C10") (pin "1") (pinfunction "1_1") (pintype "passive"))
      (node (ref "U4") (pin "6") (pinfunction "COMP_6") (pintype "bidirectional"))
    )
    (net (code "164") (name "Net-(U4-EN)") (class "Default")
      (node (ref "R13") (pin "2") (pinfunction "2_2") (pintype "passive"))
      (node (ref "U4") (pin "7") (pinfunction "EN_7") (pintype "bidirectional"))
    )
    (net (code "165") (name "Net-(U4-FB)") (class "Default")
      (node (ref "R16") (pin "1") (pinfunction "1_1") (pintype "passive"))
      (node (ref "R17") (pin "2") (pinfunction "2_2") (pintype "passive"))
      (node (ref "U4") (pin "5") (pinfunction "FB_5") (pintype "bidirectional"))
    )
    (net (code "166") (name "Net-(U4-SS)") (class "Default")
      (node (ref "C11") (pin "1") (pinfunction "1_1") (pintype "passive"))
      (node (ref "U4") (pin "8") (pinfunction "SS_8") (pintype "bidirectional"))
    )
    (net (code "167") (name "Net-(U4-SW)") (class "Default")
      (node (ref "C12") (pin "2") (pinfunction "2_2") (pintype "passive"))
      (node (ref "L1") (pin "1") (pinfunction "1_1") (pintype "passive"))
      (node (ref "U4") (pin "3") (pinfunction "SW_3") (pintype "bidirectional"))
    )
    (net (code "168") (name "Net-(U4-VIN)") (class "Default")
      (node (ref "C8") (pin "1") (pinfunction "1_1") (pintype "passive"))
      (node (ref "C9") (pin "1") (pinfunction "1_1") (pintype "passive"))
      (node (ref "D6") (pin "C") (pinfunction "C_C") (pintype "passive"))
      (node (ref "F1") (pin "2") (pinfunction "2_2") (pintype "passive"))
      (node (ref "R13") (pin "1") (pinfunction "1_1") (pintype "passive"))
      (node (ref "U4") (pin "2") (pinfunction "VIN_2") (pintype "bidirectional"))
    )
    (net (code "169") (name "Net-(U6-XTAL1)") (class "Default")
      (node (ref "C20") (pin "1") (pinfunction "1_1") (pintype "passive"))
      (node (ref "U6") (pin "34") (pinfunction "XTAL1_34") (pintype "input"))
      (node (ref "X1") (pin "1") (pinfunction "1_1") (pintype "passive"))
    )
    (net (code "170") (name "Net-(U6-XTAL2)") (class "Default")
      (node (ref "C19") (pin "1") (pinfunction "1_1") (pintype "passive"))
      (node (ref "U6") (pin "33") (pinfunction "XTAL2_33") (pintype "output"))
      (node (ref "X1") (pin "2") (pinfunction "2_2") (pintype "passive"))
    )
    (net (code "171") (name "Net-(U7-A8)") (class "Default")
      (node (ref "R62") (pin "1") (pinfunction "1_1") (pintype "passive"))
      (node (ref "U7") (pin "9") (pinfunction "A8_9") (pintype "bidirectional"))
    )
    (net (code "172") (name "Net-(U7-OE)") (class "Default")
      (node (ref "R47") (pin "1") (pinfunction "1_1") (pintype "passive"))
      (node (ref "R48") (pin "1") (pinfunction "1_1") (pintype "passive"))
      (node (ref "U7") (pin "10") (pinfunction "OE_10") (pintype "bidirectional"))
    )
    (net (code "173") (name "Net-(U8-A2)") (class "Default")
      (node (ref "R51") (pin "1") (pinfunction "1_1") (pintype "passive"))
      (node (ref "U8") (pin "3") (pinfunction "A2_3") (pintype "input"))
    )
    (net (code "174") (name "Net-(U8-WP)") (class "Default")
      (node (ref "R52") (pin "1") (pinfunction "1_1") (pintype "passive"))
      (node (ref "R67") (pin "2") (pinfunction "2_2") (pintype "passive"))
      (node (ref "U8") (pin "7") (pinfunction "WP_7") (pintype "bidirectional"))
    )
    (net (code "175") (name "Net-(U9-IN-)") (class "Default")
      (node (ref "C39") (pin "+") (pinfunction "+_+") (pintype "passive"))
      (node (ref "J14") (pin "PWR1") (pinfunction "S_PWR1") (pintype "passive"))
      (node (ref "J14") (pin "PWR2") (pinfunction "S_PWR2") (pintype "passive"))
      (node (ref "R59") (pin "2") (pinfunction "2_2") (pintype "passive"))
      (node (ref "U9") (pin "5") (pinfunction "IN-_5") (pintype "input"))
    )
    (net (code "176") (name "Net-(U9-VOUT)") (class "Default")
      (node (ref "R49") (pin "1") (pinfunction "1_1") (pintype "passive"))
      (node (ref "U9") (pin "6") (pinfunction "VOUT_6") (pintype "output"))
    )
    (net (code "177") (name "Net-(U10-IN-)") (class "Default")
      (node (ref "C40") (pin "+") (pinfunction "+_+") (pintype "passive"))
      (node (ref "J15") (pin "PWR1") (pinfunction "S_PWR1") (pintype "passive"))
      (node (ref "J15") (pin "PWR2") (pinfunction "S_PWR2") (pintype "passive"))
      (node (ref "R60") (pin "2") (pinfunction "2_2") (pintype "passive"))
      (node (ref "U10") (pin "5") (pinfunction "IN-_5") (pintype "input"))
    )
    (net (code "178") (name "Net-(U10-VOUT)") (class "Default")
      (node (ref "R50") (pin "1") (pinfunction "1_1") (pintype "passive"))
      (node (ref "U10") (pin "6") (pinfunction "VOUT_6") (pintype "output"))
    )
    (net (code "179") (name "Net-(U11-IN-)") (class "Default")
      (node (ref "C41") (pin "+") (pinfunction "+_+") (pintype "passive"))
      (node (ref "J16") (pin "PWR1") (pinfunction "S_PWR1") (pintype "passive"))
      (node (ref "J16") (pin "PWR2") (pinfunction "S_PWR2") (pintype "passive"))
      (node (ref "R61") (pin "2") (pinfunction "2_2") (pintype "passive"))
      (node (ref "U11") (pin "5") (pinfunction "IN-_5") (pintype "input"))
    )
    (net (code "180") (name "Net-(U11-VOUT)") (class "Default")
      (node (ref "R66") (pin "1") (pinfunction "1_1") (pintype "passive"))
      (node (ref "U11") (pin "6") (pinfunction "VOUT_6") (pintype "output"))
    )
    (net (code "181") (name "PWM_1+") (class "Default")
      (node (ref "D7") (pin "C") (pinfunction "C_C") (pintype "passive"))
      (node (ref "J1") (pin "1") (pinfunction "1_1") (pintype "passive"))
      (node (ref "R24") (pin "2") (pinfunction "2_2") (pintype "passive"))
      (node (ref "R25") (pin "2") (pinfunction "2_2") (pintype "passive"))
      (node (ref "R26") (pin "2") (pinfunction "2_2") (pintype "passive"))
    )
    (net (code "182") (name "PWM_1-") (class "Default")
      (node (ref "D7") (pin "A") (pinfunction "A_A") (pintype "passive"))
      (node (ref "J1") (pin "2") (pinfunction "1_2") (pintype "passive"))
      (node (ref "Q4") (pin "3") (pinfunction "D_3") (pintype "passive"))
    )
    (net (code "183") (name "PWM_2+") (class "Default")
      (node (ref "D8") (pin "C") (pinfunction "C_C") (pintype "passive"))
      (node (ref "J1") (pin "3") (pinfunction "1_3") (pintype "passive"))
      (node (ref "R27") (pin "2") (pinfunction "2_2") (pintype "passive"))
      (node (ref "R28") (pin "2") (pinfunction "2_2") (pintype "passive"))
      (node (ref "R29") (pin "2") (pinfunction "2_2") (pintype "passive"))
    )
    (net (code "184") (name "PWM_2-") (class "Default")
      (node (ref "D8") (pin "A") (pinfunction "A_A") (pintype "passive"))
      (node (ref "J1") (pin "4") (pinfunction "1_4") (pintype "passive"))
      (node (ref "Q5") (pin "3") (pinfunction "D_3") (pintype "passive"))
    )
    (net (code "185") (name "PWM_3+") (class "Default")
      (node (ref "D9") (pin "C") (pinfunction "C_C") (pintype "passive"))
      (node (ref "J1") (pin "5") (pinfunction "1_5") (pintype "passive"))
      (node (ref "R30") (pin "2") (pinfunction "2_2") (pintype "passive"))
      (node (ref "R31") (pin "2") (pinfunction "2_2") (pintype "passive"))
      (node (ref "R32") (pin "2") (pinfunction "2_2") (pintype "passive"))
    )
    (net (code "186") (name "PWM_3-") (class "Default")
      (node (ref "D9") (pin "A") (pinfunction "A_A") (pintype "passive"))
      (node (ref "J1") (pin "6") (pinfunction "1_6") (pintype "passive"))
      (node (ref "Q6") (pin "3") (pinfunction "D_3") (pintype "passive"))
    )
    (net (code "187") (name "PWM_4+") (class "Default")
      (node (ref "D10") (pin "C") (pinfunction "C_C") (pintype "passive"))
      (node (ref "J1") (pin "7") (pinfunction "1_7") (pintype "passive"))
      (node (ref "R33") (pin "2") (pinfunction "2_2") (pintype "passive"))
      (node (ref "R34") (pin "2") (pinfunction "2_2") (pintype "passive"))
      (node (ref "R35") (pin "2") (pinfunction "2_2") (pintype "passive"))
    )
    (net (code "188") (name "PWM_4-") (class "Default")
      (node (ref "D10") (pin "A") (pinfunction "A_A") (pintype "passive"))
      (node (ref "J1") (pin "8") (pinfunction "1_8") (pintype "passive"))
      (node (ref "Q7") (pin "3") (pinfunction "D_3") (pintype "passive"))
    )
    (net (code "189") (name "RESET_N") (class "Default")
      (node (ref "J13") (pin "5") (pinfunction "5_5") (pintype "passive"))
      (node (ref "R20") (pin "2") (pinfunction "2_2") (pintype "passive"))
      (node (ref "U6") (pin "30") (pinfunction "RESET_30") (pintype "input"))
      (node (ref "U7") (pin "13") (pinfunction "B7_13") (pintype "bidirectional"))
    )
    (net (code "190") (name "TETHER_A") (class "Default")
      (node (ref "FB1") (pin "1") (pinfunction "1_1") (pintype "passive"))
      (node (ref "J10") (pin "1") (pinfunction "S_1") (pintype "passive"))
      (node (ref "J19") (pin "1") (pinfunction "1_1") (pintype "passive"))
      (node (ref "J19") (pin "2") (pinfunction "1_2") (pintype "passive"))
      (node (ref "J5") (pin "18") (pinfunction "18_18") (pintype "passive"))
    )
    (net (code "191") (name "TETHER_B") (class "Default")
      (node (ref "C5") (pin "2") (pinfunction "2_2") (pintype "passive"))
      (node (ref "J10") (pin "3") (pinfunction "S_3") (pintype "passive"))
      (node (ref "J19") (pin "5") (pinfunction "1_5") (pintype "passive"))
      (node (ref "J19") (pin "6") (pinfunction "1_6") (pintype "passive"))
      (node (ref "J5") (pin "19") (pinfunction "19_19") (pintype "passive"))
      (node (ref "OC1") (pin "2") (pinfunction "IN-B_2") (pintype "passive"))
    )
    (net (code "192") (name "V_BAT") (class "Default")
      (node (ref "F1") (pin "1") (pinfunction "1_1") (pintype "passive"))
      (node (ref "R12") (pin "2") (pinfunction "2_2") (pintype "passive"))
      (node (ref "R26") (pin "1") (pinfunction "1_1") (pintype "passive"))
      (node (ref "R29") (pin "1") (pinfunction "1_1") (pintype "passive"))
      (node (ref "R32") (pin "1") (pinfunction "1_1") (pintype "passive"))
      (node (ref "R35") (pin "1") (pinfunction "1_1") (pintype "passive"))
      (node (ref "U3") (pin "5") (pinfunction "IN-_5") (pintype "input"))
    )
    (net (code "193") (name "unconnected-(J10B-S-Pad2)") (class "Default")
      (node (ref "J10") (pin "2") (pinfunction "S_2") (pintype "passive"))
    )
    (net (code "194") (name "unconnected-(J19C-1-Pad3)") (class "Default")
      (node (ref "J19") (pin "3") (pinfunction "1_3") (pintype "passive"))
    )
    (net (code "195") (name "unconnected-(J19D-1-Pad4)") (class "Default")
      (node (ref "J19") (pin "4") (pinfunction "1_4") (pintype "passive"))
    )
    (net (code "196") (name "unconnected-(U6-(CLKO{slash}ICP3{slash}INT7)PE7-Pad9)") (class "Default")
      (node (ref "U6") (pin "9") (pinfunction "(CLKO/ICP3/INT7)PE7_9") (pintype "bidirectional"))
    )
    (net (code "197") (name "unconnected-(U6-(ICP1)PD4-Pad47)") (class "Default")
      (node (ref "U6") (pin "47") (pinfunction "(ICP1)PD4_47") (pintype "bidirectional"))
    )
    (net (code "198") (name "unconnected-(U6-(T1)PD6-Pad49)") (class "Default")
      (node (ref "U6") (pin "49") (pinfunction "(T1)PD6_49") (pintype "bidirectional"))
    )
    (net (code "199") (name "unconnected-(U6-(T3{slash}INT6)PE6-Pad8)") (class "Default")
      (node (ref "U6") (pin "8") (pinfunction "(T3/INT6)PE6_8") (pintype "bidirectional"))
    )
    (net (code "200") (name "unconnected-(U6-(TOSC1)PG4-Pad29)") (class "Default")
      (node (ref "U6") (pin "29") (pinfunction "(TOSC1)PG4_29") (pintype "bidirectional"))
    )
    (net (code "201") (name "unconnected-(U6-(TOSC2)PG3-Pad28)") (class "Default")
      (node (ref "U6") (pin "28") (pinfunction "(TOSC2)PG3_28") (pintype "bidirectional"))
    )
    (net (code "202") (name "unconnected-(U6-(XCK0{slash}AIN0)PE2-Pad4)") (class "Default")
      (node (ref "U6") (pin "4") (pinfunction "(XCK0/AIN0)PE2_4") (pintype "bidirectional"))
    )
    (net (code "203") (name "unconnected-(U6-(XCK1)PD5-Pad48)") (class "Default")
      (node (ref "U6") (pin "48") (pinfunction "(XCK1)PD5_48") (pintype "bidirectional"))
    )
    (net (code "204") (name "unconnected-(U6-PH2(XCK2)-Pad14)") (class "Default")
      (node (ref "U6") (pin "14") (pinfunction "PH2(XCK2)_14") (pintype "bidirectional"))
    )
    (net (code "205") (name "unconnected-(U6-PH7(T4)-Pad27)") (class "Default")
      (node (ref "U6") (pin "27") (pinfunction "PH7(T4)_27") (pintype "bidirectional"))
    )
    (net (code "206") (name "unconnected-(U6-PJ2(XCK3{slash}PCINT11)-Pad65)") (class "Default")
      (node (ref "U6") (pin "65") (pinfunction "PJ2(XCK3/PCINT11)_65") (pintype "bidirectional"))
    )
    (net (code "207") (name "unconnected-(U6-PJ3(PCINT12)-Pad66)") (class "Default")
      (node (ref "U6") (pin "66") (pinfunction "PJ3(PCINT12)_66") (pintype "bidirectional"))
    )
    (net (code "208") (name "unconnected-(U6-PJ4(PCINT13)-Pad67)") (class "Default")
      (node (ref "U6") (pin "67") (pinfunction "PJ4(PCINT13)_67") (pintype "bidirectional"))
    )
    (net (code "209") (name "unconnected-(U6-PJ5(PCINT14)-Pad68)") (class "Default")
      (node (ref "U6") (pin "68") (pinfunction "PJ5(PCINT14)_68") (pintype "bidirectional"))
    )
    (net (code "210") (name "unconnected-(U6-PJ6(PCINT15)-Pad69)") (class "Default")
      (node (ref "U6") (pin "69") (pinfunction "PJ6(PCINT15)_69") (pintype "bidirectional"))
    )
    (net (code "211") (name "unconnected-(U6-PJ7-Pad79)") (class "Default")
      (node (ref "U6") (pin "79") (pinfunction "PJ7_79") (pintype "bidirectional"))
    )
    (net (code "212") (name "unconnected-(U7-B8-Pad12)") (class "Default")
      (node (ref "U7") (pin "12") (pinfunction "B8_12") (pintype "bidirectional"))
    )
  )
)
